# ProPrj_15_v2_0_2025-09-09.net
KiCad netlist of a schematic drawn in EasyEDA Pro
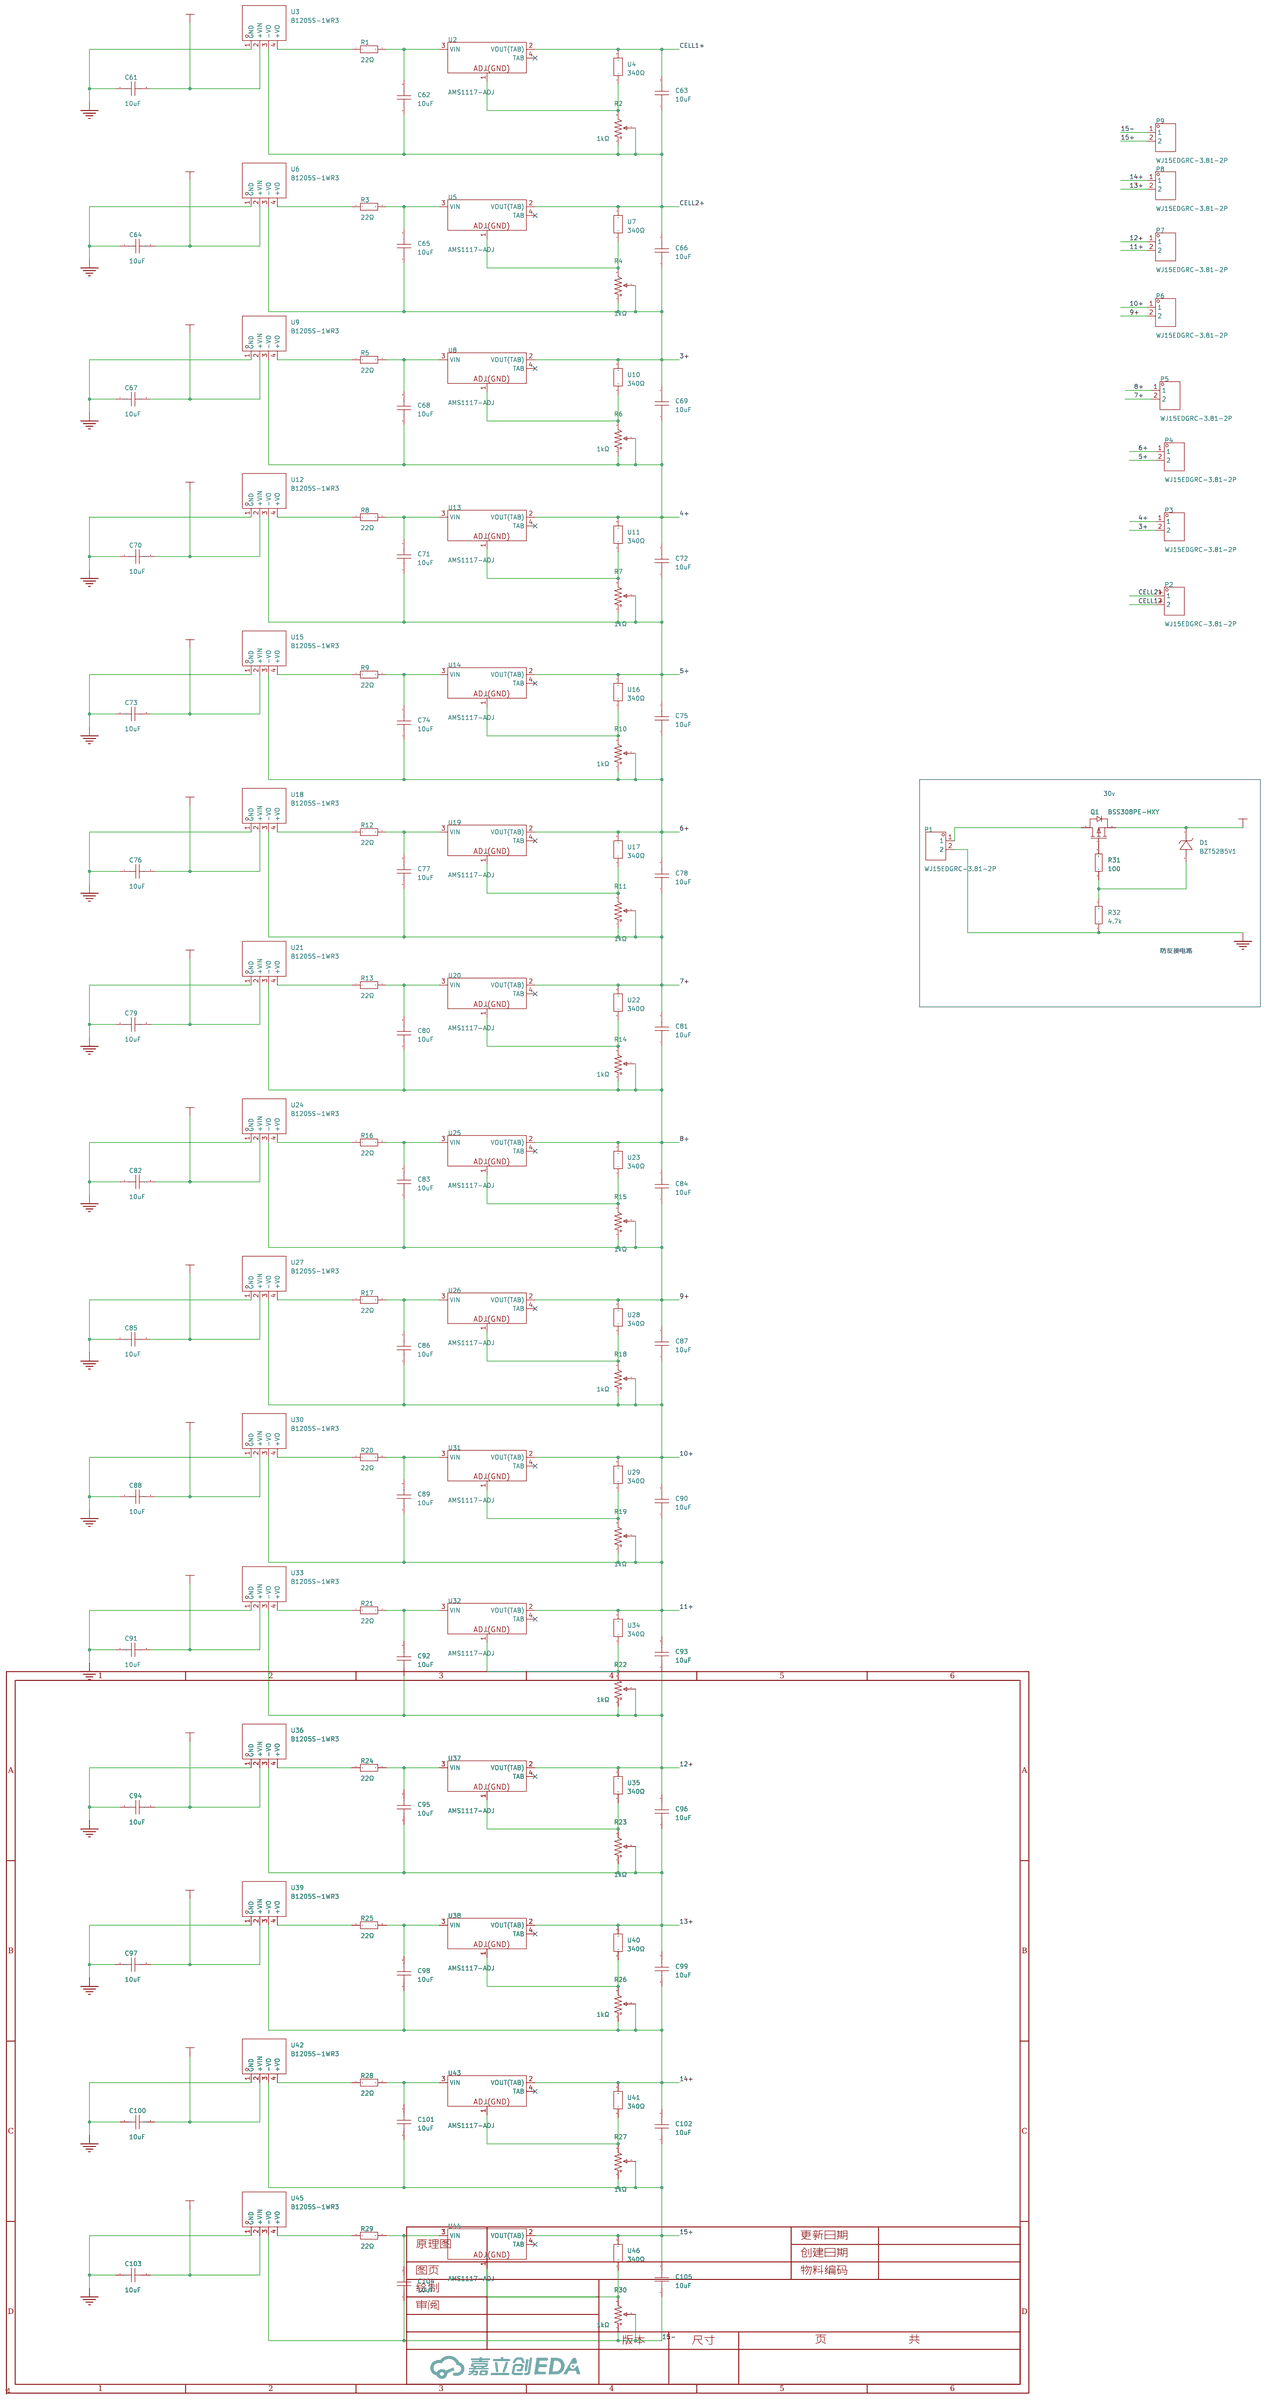
[diagram p0: schematic sheet]

(export (version "E")
  (design (tool "Eeschema 10.0.6"))
  (components
    (comp (ref "C61")
      (value "10uF")
      (footprint "easyedapro:C0805")
      (description "容值:10uF;精度:±10%;额定电压:25V;材质(温度系数):X5R;")
      (fields
        (field (name "Manufacturer Part") "CL21A106KAYNNNE")
        (field (name "Manufacturer") "SAMSUNG(三星)")
      )
      (libsource (lib "easyedapro") (part "CL21A106KAYNNNE"))
    )
    (comp (ref "C62")
      (value "10uF")
      (footprint "easyedapro:C0805")
      (description "容值:10uF;精度:±10%;额定电压:25V;材质(温度系数):X5R;")
      (fields
        (field (name "Manufacturer Part") "CL21A106KAYNNNE")
        (field (name "Manufacturer") "SAMSUNG(三星)")
      )
      (libsource (lib "easyedapro") (part "CL21A106KAYNNNE"))
    )
    (comp (ref "C63")
      (value "10uF")
      (footprint "easyedapro:C0805")
      (description "容值:10uF;精度:±10%;额定电压:25V;材质(温度系数):X5R;")
      (fields
        (field (name "Manufacturer Part") "CL21A106KAYNNNE")
        (field (name "Manufacturer") "SAMSUNG(三星)")
      )
      (libsource (lib "easyedapro") (part "CL21A106KAYNNNE"))
    )
    (comp (ref "C64")
      (value "10uF")
      (footprint "easyedapro:C0805")
      (description "容值:10uF;精度:±10%;额定电压:25V;材质(温度系数):X5R;")
      (fields
        (field (name "Manufacturer Part") "CL21A106KAYNNNE")
        (field (name "Manufacturer") "SAMSUNG(三星)")
      )
      (libsource (lib "easyedapro") (part "CL21A106KAYNNNE"))
    )
    (comp (ref "C65")
      (value "10uF")
      (footprint "easyedapro:C0805")
      (description "容值:10uF;精度:±10%;额定电压:25V;材质(温度系数):X5R;")
      (fields
        (field (name "Manufacturer Part") "CL21A106KAYNNNE")
        (field (name "Manufacturer") "SAMSUNG(三星)")
      )
      (libsource (lib "easyedapro") (part "CL21A106KAYNNNE"))
    )
    (comp (ref "C66")
      (value "10uF")
      (footprint "easyedapro:C0805")
      (description "容值:10uF;精度:±10%;额定电压:25V;材质(温度系数):X5R;")
      (fields
        (field (name "Manufacturer Part") "CL21A106KAYNNNE")
        (field (name "Manufacturer") "SAMSUNG(三星)")
      )
      (libsource (lib "easyedapro") (part "CL21A106KAYNNNE"))
    )
    (comp (ref "C67")
      (value "10uF")
      (footprint "easyedapro:C0805")
      (description "容值:10uF;精度:±10%;额定电压:25V;材质(温度系数):X5R;")
      (fields
        (field (name "Manufacturer Part") "CL21A106KAYNNNE")
        (field (name "Manufacturer") "SAMSUNG(三星)")
      )
      (libsource (lib "easyedapro") (part "CL21A106KAYNNNE"))
    )
    (comp (ref "C68")
      (value "10uF")
      (footprint "easyedapro:C0805")
      (description "容值:10uF;精度:±10%;额定电压:25V;材质(温度系数):X5R;")
      (fields
        (field (name "Manufacturer Part") "CL21A106KAYNNNE")
        (field (name "Manufacturer") "SAMSUNG(三星)")
      )
      (libsource (lib "easyedapro") (part "CL21A106KAYNNNE"))
    )
    (comp (ref "C69")
      (value "10uF")
      (footprint "easyedapro:C0805")
      (description "容值:10uF;精度:±10%;额定电压:25V;材质(温度系数):X5R;")
      (fields
        (field (name "Manufacturer Part") "CL21A106KAYNNNE")
        (field (name "Manufacturer") "SAMSUNG(三星)")
      )
      (libsource (lib "easyedapro") (part "CL21A106KAYNNNE"))
    )
    (comp (ref "C70")
      (value "10uF")
      (footprint "easyedapro:C0805")
      (description "容值:10uF;精度:±10%;额定电压:25V;材质(温度系数):X5R;")
      (fields
        (field (name "Manufacturer Part") "CL21A106KAYNNNE")
        (field (name "Manufacturer") "SAMSUNG(三星)")
      )
      (libsource (lib "easyedapro") (part "CL21A106KAYNNNE"))
    )
    (comp (ref "C71")
      (value "10uF")
      (footprint "easyedapro:C0805")
      (description "容值:10uF;精度:±10%;额定电压:25V;材质(温度系数):X5R;")
      (fields
        (field (name "Manufacturer Part") "CL21A106KAYNNNE")
        (field (name "Manufacturer") "SAMSUNG(三星)")
      )
      (libsource (lib "easyedapro") (part "CL21A106KAYNNNE"))
    )
    (comp (ref "C72")
      (value "10uF")
      (footprint "easyedapro:C0805")
      (description "容值:10uF;精度:±10%;额定电压:25V;材质(温度系数):X5R;")
      (fields
        (field (name "Manufacturer Part") "CL21A106KAYNNNE")
        (field (name "Manufacturer") "SAMSUNG(三星)")
      )
      (libsource (lib "easyedapro") (part "CL21A106KAYNNNE"))
    )
    (comp (ref "C73")
      (value "10uF")
      (footprint "easyedapro:C0805")
      (description "容值:10uF;精度:±10%;额定电压:25V;材质(温度系数):X5R;")
      (fields
        (field (name "Manufacturer Part") "CL21A106KAYNNNE")
        (field (name "Manufacturer") "SAMSUNG(三星)")
      )
      (libsource (lib "easyedapro") (part "CL21A106KAYNNNE"))
    )
    (comp (ref "C74")
      (value "10uF")
      (footprint "easyedapro:C0805")
      (description "容值:10uF;精度:±10%;额定电压:25V;材质(温度系数):X5R;")
      (fields
        (field (name "Manufacturer Part") "CL21A106KAYNNNE")
        (field (name "Manufacturer") "SAMSUNG(三星)")
      )
      (libsource (lib "easyedapro") (part "CL21A106KAYNNNE"))
    )
    (comp (ref "C75")
      (value "10uF")
      (footprint "easyedapro:C0805")
      (description "容值:10uF;精度:±10%;额定电压:25V;材质(温度系数):X5R;")
      (fields
        (field (name "Manufacturer Part") "CL21A106KAYNNNE")
        (field (name "Manufacturer") "SAMSUNG(三星)")
      )
      (libsource (lib "easyedapro") (part "CL21A106KAYNNNE"))
    )
    (comp (ref "C76")
      (value "10uF")
      (footprint "easyedapro:C0805")
      (description "容值:10uF;精度:±10%;额定电压:25V;材质(温度系数):X5R;")
      (fields
        (field (name "Manufacturer Part") "CL21A106KAYNNNE")
        (field (name "Manufacturer") "SAMSUNG(三星)")
      )
      (libsource (lib "easyedapro") (part "CL21A106KAYNNNE"))
    )
    (comp (ref "C77")
      (value "10uF")
      (footprint "easyedapro:C0805")
      (description "容值:10uF;精度:±10%;额定电压:25V;材质(温度系数):X5R;")
      (fields
        (field (name "Manufacturer Part") "CL21A106KAYNNNE")
        (field (name "Manufacturer") "SAMSUNG(三星)")
      )
      (libsource (lib "easyedapro") (part "CL21A106KAYNNNE"))
    )
    (comp (ref "C78")
      (value "10uF")
      (footprint "easyedapro:C0805")
      (description "容值:10uF;精度:±10%;额定电压:25V;材质(温度系数):X5R;")
      (fields
        (field (name "Manufacturer Part") "CL21A106KAYNNNE")
        (field (name "Manufacturer") "SAMSUNG(三星)")
      )
      (libsource (lib "easyedapro") (part "CL21A106KAYNNNE"))
    )
    (comp (ref "C79")
      (value "10uF")
      (footprint "easyedapro:C0805")
      (description "容值:10uF;精度:±10%;额定电压:25V;材质(温度系数):X5R;")
      (fields
        (field (name "Manufacturer Part") "CL21A106KAYNNNE")
        (field (name "Manufacturer") "SAMSUNG(三星)")
      )
      (libsource (lib "easyedapro") (part "CL21A106KAYNNNE"))
    )
    (comp (ref "C80")
      (value "10uF")
      (footprint "easyedapro:C0805")
      (description "容值:10uF;精度:±10%;额定电压:25V;材质(温度系数):X5R;")
      (fields
        (field (name "Manufacturer Part") "CL21A106KAYNNNE")
        (field (name "Manufacturer") "SAMSUNG(三星)")
      )
      (libsource (lib "easyedapro") (part "CL21A106KAYNNNE"))
    )
    (comp (ref "C81")
      (value "10uF")
      (footprint "easyedapro:C0805")
      (description "容值:10uF;精度:±10%;额定电压:25V;材质(温度系数):X5R;")
      (fields
        (field (name "Manufacturer Part") "CL21A106KAYNNNE")
        (field (name "Manufacturer") "SAMSUNG(三星)")
      )
      (libsource (lib "easyedapro") (part "CL21A106KAYNNNE"))
    )
    (comp (ref "C82")
      (value "10uF")
      (footprint "easyedapro:C0805")
      (description "容值:10uF;精度:±10%;额定电压:25V;材质(温度系数):X5R;")
      (fields
        (field (name "Manufacturer Part") "CL21A106KAYNNNE")
        (field (name "Manufacturer") "SAMSUNG(三星)")
      )
      (libsource (lib "easyedapro") (part "CL21A106KAYNNNE"))
    )
    (comp (ref "C83")
      (value "10uF")
      (footprint "easyedapro:C0805")
      (description "容值:10uF;精度:±10%;额定电压:25V;材质(温度系数):X5R;")
      (fields
        (field (name "Manufacturer Part") "CL21A106KAYNNNE")
        (field (name "Manufacturer") "SAMSUNG(三星)")
      )
      (libsource (lib "easyedapro") (part "CL21A106KAYNNNE"))
    )
    (comp (ref "C84")
      (value "10uF")
      (footprint "easyedapro:C0805")
      (description "容值:10uF;精度:±10%;额定电压:25V;材质(温度系数):X5R;")
      (fields
        (field (name "Manufacturer Part") "CL21A106KAYNNNE")
        (field (name "Manufacturer") "SAMSUNG(三星)")
      )
      (libsource (lib "easyedapro") (part "CL21A106KAYNNNE"))
    )
    (comp (ref "C85")
      (value "10uF")
      (footprint "easyedapro:C0805")
      (description "容值:10uF;精度:±10%;额定电压:25V;材质(温度系数):X5R;")
      (fields
        (field (name "Manufacturer Part") "CL21A106KAYNNNE")
        (field (name "Manufacturer") "SAMSUNG(三星)")
      )
      (libsource (lib "easyedapro") (part "CL21A106KAYNNNE"))
    )
    (comp (ref "C86")
      (value "10uF")
      (footprint "easyedapro:C0805")
      (description "容值:10uF;精度:±10%;额定电压:25V;材质(温度系数):X5R;")
      (fields
        (field (name "Manufacturer Part") "CL21A106KAYNNNE")
        (field (name "Manufacturer") "SAMSUNG(三星)")
      )
      (libsource (lib "easyedapro") (part "CL21A106KAYNNNE"))
    )
    (comp (ref "C87")
      (value "10uF")
      (footprint "easyedapro:C0805")
      (description "容值:10uF;精度:±10%;额定电压:25V;材质(温度系数):X5R;")
      (fields
        (field (name "Manufacturer Part") "CL21A106KAYNNNE")
        (field (name "Manufacturer") "SAMSUNG(三星)")
      )
      (libsource (lib "easyedapro") (part "CL21A106KAYNNNE"))
    )
    (comp (ref "C88")
      (value "10uF")
      (footprint "easyedapro:C0805")
      (description "容值:10uF;精度:±10%;额定电压:25V;材质(温度系数):X5R;")
      (fields
        (field (name "Manufacturer Part") "CL21A106KAYNNNE")
        (field (name "Manufacturer") "SAMSUNG(三星)")
      )
      (libsource (lib "easyedapro") (part "CL21A106KAYNNNE"))
    )
    (comp (ref "C89")
      (value "10uF")
      (footprint "easyedapro:C0805")
      (description "容值:10uF;精度:±10%;额定电压:25V;材质(温度系数):X5R;")
      (fields
        (field (name "Manufacturer Part") "CL21A106KAYNNNE")
        (field (name "Manufacturer") "SAMSUNG(三星)")
      )
      (libsource (lib "easyedapro") (part "CL21A106KAYNNNE"))
    )
    (comp (ref "C90")
      (value "10uF")
      (footprint "easyedapro:C0805")
      (description "容值:10uF;精度:±10%;额定电压:25V;材质(温度系数):X5R;")
      (fields
        (field (name "Manufacturer Part") "CL21A106KAYNNNE")
        (field (name "Manufacturer") "SAMSUNG(三星)")
      )
      (libsource (lib "easyedapro") (part "CL21A106KAYNNNE"))
    )
    (comp (ref "C91")
      (value "10uF")
      (footprint "easyedapro:C0805")
      (description "容值:10uF;精度:±10%;额定电压:25V;材质(温度系数):X5R;")
      (fields
        (field (name "Manufacturer Part") "CL21A106KAYNNNE")
        (field (name "Manufacturer") "SAMSUNG(三星)")
      )
      (libsource (lib "easyedapro") (part "CL21A106KAYNNNE"))
    )
    (comp (ref "C92")
      (value "10uF")
      (footprint "easyedapro:C0805")
      (description "容值:10uF;精度:±10%;额定电压:25V;材质(温度系数):X5R;")
      (fields
        (field (name "Manufacturer Part") "CL21A106KAYNNNE")
        (field (name "Manufacturer") "SAMSUNG(三星)")
      )
      (libsource (lib "easyedapro") (part "CL21A106KAYNNNE"))
    )
    (comp (ref "C93")
      (value "10uF")
      (footprint "easyedapro:C0805")
      (description "容值:10uF;精度:±10%;额定电压:25V;材质(温度系数):X5R;")
      (fields
        (field (name "Manufacturer Part") "CL21A106KAYNNNE")
        (field (name "Manufacturer") "SAMSUNG(三星)")
      )
      (libsource (lib "easyedapro") (part "CL21A106KAYNNNE"))
    )
    (comp (ref "C94")
      (value "10uF")
      (footprint "easyedapro:C0805")
      (description "容值:10uF;精度:±10%;额定电压:25V;材质(温度系数):X5R;")
      (fields
        (field (name "Manufacturer Part") "CL21A106KAYNNNE")
        (field (name "Manufacturer") "SAMSUNG(三星)")
      )
      (libsource (lib "easyedapro") (part "CL21A106KAYNNNE"))
    )
    (comp (ref "C95")
      (value "10uF")
      (footprint "easyedapro:C0805")
      (description "容值:10uF;精度:±10%;额定电压:25V;材质(温度系数):X5R;")
      (fields
        (field (name "Manufacturer Part") "CL21A106KAYNNNE")
        (field (name "Manufacturer") "SAMSUNG(三星)")
      )
      (libsource (lib "easyedapro") (part "CL21A106KAYNNNE"))
    )
    (comp (ref "C96")
      (value "10uF")
      (footprint "easyedapro:C0805")
      (description "容值:10uF;精度:±10%;额定电压:25V;材质(温度系数):X5R;")
      (fields
        (field (name "Manufacturer Part") "CL21A106KAYNNNE")
        (field (name "Manufacturer") "SAMSUNG(三星)")
      )
      (libsource (lib "easyedapro") (part "CL21A106KAYNNNE"))
    )
    (comp (ref "C97")
      (value "10uF")
      (footprint "easyedapro:C0805")
      (description "容值:10uF;精度:±10%;额定电压:25V;材质(温度系数):X5R;")
      (fields
        (field (name "Manufacturer Part") "CL21A106KAYNNNE")
        (field (name "Manufacturer") "SAMSUNG(三星)")
      )
      (libsource (lib "easyedapro") (part "CL21A106KAYNNNE"))
    )
    (comp (ref "C98")
      (value "10uF")
      (footprint "easyedapro:C0805")
      (description "容值:10uF;精度:±10%;额定电压:25V;材质(温度系数):X5R;")
      (fields
        (field (name "Manufacturer Part") "CL21A106KAYNNNE")
        (field (name "Manufacturer") "SAMSUNG(三星)")
      )
      (libsource (lib "easyedapro") (part "CL21A106KAYNNNE"))
    )
    (comp (ref "C99")
      (value "10uF")
      (footprint "easyedapro:C0805")
      (description "容值:10uF;精度:±10%;额定电压:25V;材质(温度系数):X5R;")
      (fields
        (field (name "Manufacturer Part") "CL21A106KAYNNNE")
        (field (name "Manufacturer") "SAMSUNG(三星)")
      )
      (libsource (lib "easyedapro") (part "CL21A106KAYNNNE"))
    )
    (comp (ref "C100")
      (value "10uF")
      (footprint "easyedapro:C0805")
      (description "容值:10uF;精度:±10%;额定电压:25V;材质(温度系数):X5R;")
      (fields
        (field (name "Manufacturer Part") "CL21A106KAYNNNE")
        (field (name "Manufacturer") "SAMSUNG(三星)")
      )
      (libsource (lib "easyedapro") (part "CL21A106KAYNNNE"))
    )
    (comp (ref "C101")
      (value "10uF")
      (footprint "easyedapro:C0805")
      (description "容值:10uF;精度:±10%;额定电压:25V;材质(温度系数):X5R;")
      (fields
        (field (name "Manufacturer Part") "CL21A106KAYNNNE")
        (field (name "Manufacturer") "SAMSUNG(三星)")
      )
      (libsource (lib "easyedapro") (part "CL21A106KAYNNNE"))
    )
    (comp (ref "C102")
      (value "10uF")
      (footprint "easyedapro:C0805")
      (description "容值:10uF;精度:±10%;额定电压:25V;材质(温度系数):X5R;")
      (fields
        (field (name "Manufacturer Part") "CL21A106KAYNNNE")
        (field (name "Manufacturer") "SAMSUNG(三星)")
      )
      (libsource (lib "easyedapro") (part "CL21A106KAYNNNE"))
    )
    (comp (ref "C103")
      (value "10uF")
      (footprint "easyedapro:C0805")
      (description "容值:10uF;精度:±10%;额定电压:25V;材质(温度系数):X5R;")
      (fields
        (field (name "Manufacturer Part") "CL21A106KAYNNNE")
        (field (name "Manufacturer") "SAMSUNG(三星)")
      )
      (libsource (lib "easyedapro") (part "CL21A106KAYNNNE"))
    )
    (comp (ref "C104")
      (value "10uF")
      (footprint "easyedapro:C0805")
      (description "容值:10uF;精度:±10%;额定电压:25V;材质(温度系数):X5R;")
      (fields
        (field (name "Manufacturer Part") "CL21A106KAYNNNE")
        (field (name "Manufacturer") "SAMSUNG(三星)")
      )
      (libsource (lib "easyedapro") (part "CL21A106KAYNNNE"))
    )
    (comp (ref "C105")
      (value "10uF")
      (footprint "easyedapro:C0805")
      (description "容值:10uF;精度:±10%;额定电压:25V;材质(温度系数):X5R;")
      (fields
        (field (name "Manufacturer Part") "CL21A106KAYNNNE")
        (field (name "Manufacturer") "SAMSUNG(三星)")
      )
      (libsource (lib "easyedapro") (part "CL21A106KAYNNNE"))
    )
    (comp (ref "D1")
      (value "BZT52B5V1")
      (footprint "easyedapro:SOD-123_L2.7-W1.6-LS3.7-RD")
      (description "二极管配置:独立式;稳压值(标称值):5.1V;稳压值(范围):5V~5.2V;耗散功率(Pd):500mW;")
      (fields (field (name "Manufacturer") "宏嘉诚"))
      (libsource (lib "easyedapro") (part "BZT52B5V1_C19077393"))
    )
    (comp (ref "P1")
      (value "WJ15EDGRC-3.81-2P")
      (footprint "easyedapro:CONN-TH_2P-P3.81_WJ15EDGRC-3.81-2P")
      (fields (field (name "Manufacturer") "KANGNEX(康奈克斯电气)"))
      (libsource (lib "easyedapro") (part "WJ15EDGRC-3.81-2P"))
    )
    (comp (ref "P2")
      (value "WJ15EDGRC-3.81-2P")
      (footprint "easyedapro:CONN-TH_2P-P3.81_WJ15EDGRC-3.81-2P")
      (fields (field (name "Manufacturer") "KANGNEX(康奈克斯电气)"))
      (libsource (lib "easyedapro") (part "WJ15EDGRC-3.81-2P"))
    )
    (comp (ref "P3")
      (value "WJ15EDGRC-3.81-2P")
      (footprint "easyedapro:CONN-TH_2P-P3.81_WJ15EDGRC-3.81-2P")
      (fields (field (name "Manufacturer") "KANGNEX(康奈克斯电气)"))
      (libsource (lib "easyedapro") (part "WJ15EDGRC-3.81-2P"))
    )
    (comp (ref "P4")
      (value "WJ15EDGRC-3.81-2P")
      (footprint "easyedapro:CONN-TH_2P-P3.81_WJ15EDGRC-3.81-2P")
      (fields (field (name "Manufacturer") "KANGNEX(康奈克斯电气)"))
      (libsource (lib "easyedapro") (part "WJ15EDGRC-3.81-2P"))
    )
    (comp (ref "P5")
      (value "WJ15EDGRC-3.81-2P")
      (footprint "easyedapro:CONN-TH_2P-P3.81_WJ15EDGRC-3.81-2P")
      (fields (field (name "Manufacturer") "KANGNEX(康奈克斯电气)"))
      (libsource (lib "easyedapro") (part "WJ15EDGRC-3.81-2P"))
    )
    (comp (ref "P6")
      (value "WJ15EDGRC-3.81-2P")
      (footprint "easyedapro:CONN-TH_2P-P3.81_WJ15EDGRC-3.81-2P")
      (fields (field (name "Manufacturer") "KANGNEX(康奈克斯电气)"))
      (libsource (lib "easyedapro") (part "WJ15EDGRC-3.81-2P"))
    )
    (comp (ref "P7")
      (value "WJ15EDGRC-3.81-2P")
      (footprint "easyedapro:CONN-TH_2P-P3.81_WJ15EDGRC-3.81-2P")
      (fields (field (name "Manufacturer") "KANGNEX(康奈克斯电气)"))
      (libsource (lib "easyedapro") (part "WJ15EDGRC-3.81-2P"))
    )
    (comp (ref "P8")
      (value "WJ15EDGRC-3.81-2P")
      (footprint "easyedapro:CONN-TH_2P-P3.81_WJ15EDGRC-3.81-2P")
      (fields (field (name "Manufacturer") "KANGNEX(康奈克斯电气)"))
      (libsource (lib "easyedapro") (part "WJ15EDGRC-3.81-2P"))
    )
    (comp (ref "P9")
      (value "WJ15EDGRC-3.81-2P")
      (footprint "easyedapro:CONN-TH_2P-P3.81_WJ15EDGRC-3.81-2P")
      (fields (field (name "Manufacturer") "KANGNEX(康奈克斯电气)"))
      (libsource (lib "easyedapro") (part "WJ15EDGRC-3.81-2P"))
    )
    (comp (ref "Q1")
      (value "BSS308PE-HXY")
      (footprint "easyedapro:SOT-23-3_L2.9-W1.3-P1.90-LS2.4-BR")
      (fields (field (name "Manufacturer") "HXY MOSFET(华轩阳电子)"))
      (libsource (lib "easyedapro") (part "BSS308PE-HXY"))
    )
    (comp (ref "R1")
      (value "22Ω")
      (footprint "easyedapro:R0805")
      (description "电阻类型:厚膜电阻;阻值:22Ω;精度:±5%;功率:125mW;最大工作电压:150V;温度系数:±200ppm/°C;")
      (fields
        (field (name "Manufacturer Part") "0805W8J0220T5E")
        (field (name "Manufacturer") "UNI-ROYAL(厚声)")
      )
      (libsource (lib "easyedapro") (part "0805W8J0220T5E"))
    )
    (comp (ref "R2")
      (value "1kΩ")
      (footprint "easyedapro:RES-ADJ-TH_3296W")
      (description "阻值:1kΩ;精度:±10%;功率:500mW;")
      (fields (field (name "Manufacturer Part") "3296W-1-102-8mm") (field (name "Manufacturer") "BOCHEN(博晨)"))
      (libsource (lib "easyedapro") (part "3296W-1-102_C2766201"))
    )
    (comp (ref "R3")
      (value "22Ω")
      (footprint "easyedapro:R0805")
      (description "电阻类型:厚膜电阻;阻值:22Ω;精度:±5%;功率:125mW;最大工作电压:150V;温度系数:±200ppm/°C;")
      (fields
        (field (name "Manufacturer Part") "0805W8J0220T5E")
        (field (name "Manufacturer") "UNI-ROYAL(厚声)")
      )
      (libsource (lib "easyedapro") (part "0805W8J0220T5E"))
    )
    (comp (ref "R4")
      (value "1kΩ")
      (footprint "easyedapro:RES-ADJ-TH_3296W")
      (description "阻值:1kΩ;精度:±10%;功率:500mW;")
      (fields (field (name "Manufacturer Part") "3296W-1-102-8mm") (field (name "Manufacturer") "BOCHEN(博晨)"))
      (libsource (lib "easyedapro") (part "3296W-1-102_C2766201"))
    )
    (comp (ref "R5")
      (value "22Ω")
      (footprint "easyedapro:R0805")
      (description "电阻类型:厚膜电阻;阻值:22Ω;精度:±5%;功率:125mW;最大工作电压:150V;温度系数:±200ppm/°C;")
      (fields
        (field (name "Manufacturer Part") "0805W8J0220T5E")
        (field (name "Manufacturer") "UNI-ROYAL(厚声)")
      )
      (libsource (lib "easyedapro") (part "0805W8J0220T5E"))
    )
    (comp (ref "R6")
      (value "1kΩ")
      (footprint "easyedapro:RES-ADJ-TH_3296W")
      (description "阻值:1kΩ;精度:±10%;功率:500mW;")
      (fields (field (name "Manufacturer Part") "3296W-1-102-8mm") (field (name "Manufacturer") "BOCHEN(博晨)"))
      (libsource (lib "easyedapro") (part "3296W-1-102_C2766201"))
    )
    (comp (ref "R7")
      (value "1kΩ")
      (footprint "easyedapro:RES-ADJ-TH_3296W")
      (description "阻值:1kΩ;精度:±10%;功率:500mW;")
      (fields (field (name "Manufacturer Part") "3296W-1-102-8mm") (field (name "Manufacturer") "BOCHEN(博晨)"))
      (libsource (lib "easyedapro") (part "3296W-1-102_C2766201"))
    )
    (comp (ref "R8")
      (value "22Ω")
      (footprint "easyedapro:R0805")
      (description "电阻类型:厚膜电阻;阻值:22Ω;精度:±5%;功率:125mW;最大工作电压:150V;温度系数:±200ppm/°C;")
      (fields
        (field (name "Manufacturer Part") "0805W8J0220T5E")
        (field (name "Manufacturer") "UNI-ROYAL(厚声)")
      )
      (libsource (lib "easyedapro") (part "0805W8J0220T5E"))
    )
    (comp (ref "R9")
      (value "22Ω")
      (footprint "easyedapro:R0805")
      (description "电阻类型:厚膜电阻;阻值:22Ω;精度:±5%;功率:125mW;最大工作电压:150V;温度系数:±200ppm/°C;")
      (fields
        (field (name "Manufacturer Part") "0805W8J0220T5E")
        (field (name "Manufacturer") "UNI-ROYAL(厚声)")
      )
      (libsource (lib "easyedapro") (part "0805W8J0220T5E"))
    )
    (comp (ref "R10")
      (value "1kΩ")
      (footprint "easyedapro:RES-ADJ-TH_3296W")
      (description "阻值:1kΩ;精度:±10%;功率:500mW;")
      (fields (field (name "Manufacturer Part") "3296W-1-102-8mm") (field (name "Manufacturer") "BOCHEN(博晨)"))
      (libsource (lib "easyedapro") (part "3296W-1-102_C2766201"))
    )
    (comp (ref "R11")
      (value "1kΩ")
      (footprint "easyedapro:RES-ADJ-TH_3296W")
      (description "阻值:1kΩ;精度:±10%;功率:500mW;")
      (fields (field (name "Manufacturer Part") "3296W-1-102-8mm") (field (name "Manufacturer") "BOCHEN(博晨)"))
      (libsource (lib "easyedapro") (part "3296W-1-102_C2766201"))
    )
    (comp (ref "R12")
      (value "22Ω")
      (footprint "easyedapro:R0805")
      (description "电阻类型:厚膜电阻;阻值:22Ω;精度:±5%;功率:125mW;最大工作电压:150V;温度系数:±200ppm/°C;")
      (fields
        (field (name "Manufacturer Part") "0805W8J0220T5E")
        (field (name "Manufacturer") "UNI-ROYAL(厚声)")
      )
      (libsource (lib "easyedapro") (part "0805W8J0220T5E"))
    )
    (comp (ref "R13")
      (value "22Ω")
      (footprint "easyedapro:R0805")
      (description "电阻类型:厚膜电阻;阻值:22Ω;精度:±5%;功率:125mW;最大工作电压:150V;温度系数:±200ppm/°C;")
      (fields
        (field (name "Manufacturer Part") "0805W8J0220T5E")
        (field (name "Manufacturer") "UNI-ROYAL(厚声)")
      )
      (libsource (lib "easyedapro") (part "0805W8J0220T5E"))
    )
    (comp (ref "R14")
      (value "1kΩ")
      (footprint "easyedapro:RES-ADJ-TH_3296W")
      (description "阻值:1kΩ;精度:±10%;功率:500mW;")
      (fields (field (name "Manufacturer Part") "3296W-1-102-8mm") (field (name "Manufacturer") "BOCHEN(博晨)"))
      (libsource (lib "easyedapro") (part "3296W-1-102_C2766201"))
    )
    (comp (ref "R15")
      (value "1kΩ")
      (footprint "easyedapro:RES-ADJ-TH_3296W")
      (description "阻值:1kΩ;精度:±10%;功率:500mW;")
      (fields (field (name "Manufacturer Part") "3296W-1-102-8mm") (field (name "Manufacturer") "BOCHEN(博晨)"))
      (libsource (lib "easyedapro") (part "3296W-1-102_C2766201"))
    )
    (comp (ref "R16")
      (value "22Ω")
      (footprint "easyedapro:R0805")
      (description "电阻类型:厚膜电阻;阻值:22Ω;精度:±5%;功率:125mW;最大工作电压:150V;温度系数:±200ppm/°C;")
      (fields
        (field (name "Manufacturer Part") "0805W8J0220T5E")
        (field (name "Manufacturer") "UNI-ROYAL(厚声)")
      )
      (libsource (lib "easyedapro") (part "0805W8J0220T5E"))
    )
    (comp (ref "R17")
      (value "22Ω")
      (footprint "easyedapro:R0805")
      (description "电阻类型:厚膜电阻;阻值:22Ω;精度:±5%;功率:125mW;最大工作电压:150V;温度系数:±200ppm/°C;")
      (fields
        (field (name "Manufacturer Part") "0805W8J0220T5E")
        (field (name "Manufacturer") "UNI-ROYAL(厚声)")
      )
      (libsource (lib "easyedapro") (part "0805W8J0220T5E"))
    )
    (comp (ref "R18")
      (value "1kΩ")
      (footprint "easyedapro:RES-ADJ-TH_3296W")
      (description "阻值:1kΩ;精度:±10%;功率:500mW;")
      (fields (field (name "Manufacturer Part") "3296W-1-102-8mm") (field (name "Manufacturer") "BOCHEN(博晨)"))
      (libsource (lib "easyedapro") (part "3296W-1-102_C2766201"))
    )
    (comp (ref "R19")
      (value "1kΩ")
      (footprint "easyedapro:RES-ADJ-TH_3296W")
      (description "阻值:1kΩ;精度:±10%;功率:500mW;")
      (fields (field (name "Manufacturer Part") "3296W-1-102-8mm") (field (name "Manufacturer") "BOCHEN(博晨)"))
      (libsource (lib "easyedapro") (part "3296W-1-102_C2766201"))
    )
    (comp (ref "R20")
      (value "22Ω")
      (footprint "easyedapro:R0805")
      (description "电阻类型:厚膜电阻;阻值:22Ω;精度:±5%;功率:125mW;最大工作电压:150V;温度系数:±200ppm/°C;")
      (fields
        (field (name "Manufacturer Part") "0805W8J0220T5E")
        (field (name "Manufacturer") "UNI-ROYAL(厚声)")
      )
      (libsource (lib "easyedapro") (part "0805W8J0220T5E"))
    )
    (comp (ref "R21")
      (value "22Ω")
      (footprint "easyedapro:R0805")
      (description "电阻类型:厚膜电阻;阻值:22Ω;精度:±5%;功率:125mW;最大工作电压:150V;温度系数:±200ppm/°C;")
      (fields
        (field (name "Manufacturer Part") "0805W8J0220T5E")
        (field (name "Manufacturer") "UNI-ROYAL(厚声)")
      )
      (libsource (lib "easyedapro") (part "0805W8J0220T5E"))
    )
    (comp (ref "R22")
      (value "1kΩ")
      (footprint "easyedapro:RES-ADJ-TH_3296W")
      (description "阻值:1kΩ;精度:±10%;功率:500mW;")
      (fields (field (name "Manufacturer Part") "3296W-1-102-8mm") (field (name "Manufacturer") "BOCHEN(博晨)"))
      (libsource (lib "easyedapro") (part "3296W-1-102_C2766201"))
    )
    (comp (ref "R23")
      (value "1kΩ")
      (footprint "easyedapro:RES-ADJ-TH_3296W")
      (description "阻值:1kΩ;精度:±10%;功率:500mW;")
      (fields (field (name "Manufacturer Part") "3296W-1-102-8mm") (field (name "Manufacturer") "BOCHEN(博晨)"))
      (libsource (lib "easyedapro") (part "3296W-1-102_C2766201"))
    )
    (comp (ref "R24")
      (value "22Ω")
      (footprint "easyedapro:R0805")
      (description "电阻类型:厚膜电阻;阻值:22Ω;精度:±5%;功率:125mW;最大工作电压:150V;温度系数:±200ppm/°C;")
      (fields
        (field (name "Manufacturer Part") "0805W8J0220T5E")
        (field (name "Manufacturer") "UNI-ROYAL(厚声)")
      )
      (libsource (lib "easyedapro") (part "0805W8J0220T5E"))
    )
    (comp (ref "R25")
      (value "22Ω")
      (footprint "easyedapro:R0805")
      (description "电阻类型:厚膜电阻;阻值:22Ω;精度:±5%;功率:125mW;最大工作电压:150V;温度系数:±200ppm/°C;")
      (fields
        (field (name "Manufacturer Part") "0805W8J0220T5E")
        (field (name "Manufacturer") "UNI-ROYAL(厚声)")
      )
      (libsource (lib "easyedapro") (part "0805W8J0220T5E"))
    )
    (comp (ref "R26")
      (value "1kΩ")
      (footprint "easyedapro:RES-ADJ-TH_3296W")
      (description "阻值:1kΩ;精度:±10%;功率:500mW;")
      (fields (field (name "Manufacturer Part") "3296W-1-102-8mm") (field (name "Manufacturer") "BOCHEN(博晨)"))
      (libsource (lib "easyedapro") (part "3296W-1-102_C2766201"))
    )
    (comp (ref "R27")
      (value "1kΩ")
      (footprint "easyedapro:RES-ADJ-TH_3296W")
      (description "阻值:1kΩ;精度:±10%;功率:500mW;")
      (fields (field (name "Manufacturer Part") "3296W-1-102-8mm") (field (name "Manufacturer") "BOCHEN(博晨)"))
      (libsource (lib "easyedapro") (part "3296W-1-102_C2766201"))
    )
    (comp (ref "R28")
      (value "22Ω")
      (footprint "easyedapro:R0805")
      (description "电阻类型:厚膜电阻;阻值:22Ω;精度:±5%;功率:125mW;最大工作电压:150V;温度系数:±200ppm/°C;")
      (fields
        (field (name "Manufacturer Part") "0805W8J0220T5E")
        (field (name "Manufacturer") "UNI-ROYAL(厚声)")
      )
      (libsource (lib "easyedapro") (part "0805W8J0220T5E"))
    )
    (comp (ref "R29")
      (value "22Ω")
      (footprint "easyedapro:R0805")
      (description "电阻类型:厚膜电阻;阻值:22Ω;精度:±5%;功率:125mW;最大工作电压:150V;温度系数:±200ppm/°C;")
      (fields
        (field (name "Manufacturer Part") "0805W8J0220T5E")
        (field (name "Manufacturer") "UNI-ROYAL(厚声)")
      )
      (libsource (lib "easyedapro") (part "0805W8J0220T5E"))
    )
    (comp (ref "R30")
      (value "1kΩ")
      (footprint "easyedapro:RES-ADJ-TH_3296W")
      (description "阻值:1kΩ;精度:±10%;功率:500mW;")
      (fields (field (name "Manufacturer Part") "3296W-1-102-8mm") (field (name "Manufacturer") "BOCHEN(博晨)"))
      (libsource (lib "easyedapro") (part "3296W-1-102_C2766201"))
    )
    (comp (ref "R31") (value "100") (footprint "easyedapro:R0805") (libsource (lib "easyedapro") (part "电阻")))
    (comp (ref "R32")
      (value "4.7k")
      (footprint "easyedapro:R0805")
      (libsource (lib "easyedapro") (part "电阻"))
    )
    (comp (ref "U2")
      (value "AMS1117-ADJ")
      (footprint "easyedapro:SOT-223_L6.7-W3.5-P2.30-BR")
      (description "输出类型:可调;工作电压:18V;输出电压:1.25V~10V;输出电流:1A;电源纹波抑制比(PSRR):60dB@(120Hz);输出极性:正极;")
      (fields (field (name "Manufacturer") "UMW(友台半导体)"))
      (libsource (lib "easyedapro") (part "AMS1117-ADJ_C347224"))
    )
    (comp (ref "U3")
      (value "B1205S-1WR3")
      (footprint "easyedapro:PWRM-TH_BXXXXS-1WR3")
      (description "尺寸：11.6*10*6mm 保护方式：短路保护（可持续自恢复）")
      (fields (field (name "Manufacturer") "ZOEYGO(中逸光)"))
      (libsource (lib "easyedapro") (part "B1205S-1WR3_C5264430"))
    )
    (comp (ref "U4")
      (value "340Ω")
      (footprint "easyedapro:R0805")
      (description "电阻类型:厚膜电阻;阻值:340Ω;精度:±1%;功率:125mW;温度系数:±100ppm/°C;")
      (fields (field (name "Manufacturer Part") "FRC0805F3400TS") (field (name "Manufacturer") "FOJAN(富捷)"))
      (libsource (lib "easyedapro") (part "FRC0805F3400TS"))
    )
    (comp (ref "U5")
      (value "AMS1117-ADJ")
      (footprint "easyedapro:SOT-223_L6.7-W3.5-P2.30-BR")
      (description "输出类型:可调;工作电压:18V;输出电压:1.25V~10V;输出电流:1A;电源纹波抑制比(PSRR):60dB@(120Hz);输出极性:正极;")
      (fields (field (name "Manufacturer") "UMW(友台半导体)"))
      (libsource (lib "easyedapro") (part "AMS1117-ADJ_C347224"))
    )
    (comp (ref "U6")
      (value "B1205S-1WR3")
      (footprint "easyedapro:PWRM-TH_BXXXXS-1WR3")
      (description "尺寸：11.6*10*6mm 保护方式：短路保护（可持续自恢复）")
      (fields (field (name "Manufacturer") "ZOEYGO(中逸光)"))
      (libsource (lib "easyedapro") (part "B1205S-1WR3_C5264430"))
    )
    (comp (ref "U7")
      (value "340Ω")
      (footprint "easyedapro:R0805")
      (description "电阻类型:厚膜电阻;阻值:340Ω;精度:±1%;功率:125mW;温度系数:±100ppm/°C;")
      (fields (field (name "Manufacturer Part") "FRC0805F3400TS") (field (name "Manufacturer") "FOJAN(富捷)"))
      (libsource (lib "easyedapro") (part "FRC0805F3400TS"))
    )
    (comp (ref "U8")
      (value "AMS1117-ADJ")
      (footprint "easyedapro:SOT-223_L6.7-W3.5-P2.30-BR")
      (description "输出类型:可调;工作电压:18V;输出电压:1.25V~10V;输出电流:1A;电源纹波抑制比(PSRR):60dB@(120Hz);输出极性:正极;")
      (fields (field (name "Manufacturer") "UMW(友台半导体)"))
      (libsource (lib "easyedapro") (part "AMS1117-ADJ_C347224"))
    )
    (comp (ref "U9")
      (value "B1205S-1WR3")
      (footprint "easyedapro:PWRM-TH_BXXXXS-1WR3")
      (description "尺寸：11.6*10*6mm 保护方式：短路保护（可持续自恢复）")
      (fields (field (name "Manufacturer") "ZOEYGO(中逸光)"))
      (libsource (lib "easyedapro") (part "B1205S-1WR3_C5264430"))
    )
    (comp (ref "U10")
      (value "340Ω")
      (footprint "easyedapro:R0805")
      (description "电阻类型:厚膜电阻;阻值:340Ω;精度:±1%;功率:125mW;温度系数:±100ppm/°C;")
      (fields (field (name "Manufacturer Part") "FRC0805F3400TS") (field (name "Manufacturer") "FOJAN(富捷)"))
      (libsource (lib "easyedapro") (part "FRC0805F3400TS"))
    )
    (comp (ref "U11")
      (value "340Ω")
      (footprint "easyedapro:R0805")
      (description "电阻类型:厚膜电阻;阻值:340Ω;精度:±1%;功率:125mW;温度系数:±100ppm/°C;")
      (fields (field (name "Manufacturer Part") "FRC0805F3400TS") (field (name "Manufacturer") "FOJAN(富捷)"))
      (libsource (lib "easyedapro") (part "FRC0805F3400TS"))
    )
    (comp (ref "U12")
      (value "B1205S-1WR3")
      (footprint "easyedapro:PWRM-TH_BXXXXS-1WR3")
      (description "尺寸：11.6*10*6mm 保护方式：短路保护（可持续自恢复）")
      (fields (field (name "Manufacturer") "ZOEYGO(中逸光)"))
      (libsource (lib "easyedapro") (part "B1205S-1WR3_C5264430"))
    )
    (comp (ref "U13")
      (value "AMS1117-ADJ")
      (footprint "easyedapro:SOT-223_L6.7-W3.5-P2.30-BR")
      (description "输出类型:可调;工作电压:18V;输出电压:1.25V~10V;输出电流:1A;电源纹波抑制比(PSRR):60dB@(120Hz);输出极性:正极;")
      (fields (field (name "Manufacturer") "UMW(友台半导体)"))
      (libsource (lib "easyedapro") (part "AMS1117-ADJ_C347224"))
    )
    (comp (ref "U14")
      (value "AMS1117-ADJ")
      (footprint "easyedapro:SOT-223_L6.7-W3.5-P2.30-BR")
      (description "输出类型:可调;工作电压:18V;输出电压:1.25V~10V;输出电流:1A;电源纹波抑制比(PSRR):60dB@(120Hz);输出极性:正极;")
      (fields (field (name "Manufacturer") "UMW(友台半导体)"))
      (libsource (lib "easyedapro") (part "AMS1117-ADJ_C347224"))
    )
    (comp (ref "U15")
      (value "B1205S-1WR3")
      (footprint "easyedapro:PWRM-TH_BXXXXS-1WR3")
      (description "尺寸：11.6*10*6mm 保护方式：短路保护（可持续自恢复）")
      (fields (field (name "Manufacturer") "ZOEYGO(中逸光)"))
      (libsource (lib "easyedapro") (part "B1205S-1WR3_C5264430"))
    )
    (comp (ref "U16")
      (value "340Ω")
      (footprint "easyedapro:R0805")
      (description "电阻类型:厚膜电阻;阻值:340Ω;精度:±1%;功率:125mW;温度系数:±100ppm/°C;")
      (fields (field (name "Manufacturer Part") "FRC0805F3400TS") (field (name "Manufacturer") "FOJAN(富捷)"))
      (libsource (lib "easyedapro") (part "FRC0805F3400TS"))
    )
    (comp (ref "U17")
      (value "340Ω")
      (footprint "easyedapro:R0805")
      (description "电阻类型:厚膜电阻;阻值:340Ω;精度:±1%;功率:125mW;温度系数:±100ppm/°C;")
      (fields (field (name "Manufacturer Part") "FRC0805F3400TS") (field (name "Manufacturer") "FOJAN(富捷)"))
      (libsource (lib "easyedapro") (part "FRC0805F3400TS"))
    )
    (comp (ref "U18")
      (value "B1205S-1WR3")
      (footprint "easyedapro:PWRM-TH_BXXXXS-1WR3")
      (description "尺寸：11.6*10*6mm 保护方式：短路保护（可持续自恢复）")
      (fields (field (name "Manufacturer") "ZOEYGO(中逸光)"))
      (libsource (lib "easyedapro") (part "B1205S-1WR3_C5264430"))
    )
    (comp (ref "U19")
      (value "AMS1117-ADJ")
      (footprint "easyedapro:SOT-223_L6.7-W3.5-P2.30-BR")
      (description "输出类型:可调;工作电压:18V;输出电压:1.25V~10V;输出电流:1A;电源纹波抑制比(PSRR):60dB@(120Hz);输出极性:正极;")
      (fields (field (name "Manufacturer") "UMW(友台半导体)"))
      (libsource (lib "easyedapro") (part "AMS1117-ADJ_C347224"))
    )
    (comp (ref "U20")
      (value "AMS1117-ADJ")
      (footprint "easyedapro:SOT-223_L6.7-W3.5-P2.30-BR")
      (description "输出类型:可调;工作电压:18V;输出电压:1.25V~10V;输出电流:1A;电源纹波抑制比(PSRR):60dB@(120Hz);输出极性:正极;")
      (fields (field (name "Manufacturer") "UMW(友台半导体)"))
      (libsource (lib "easyedapro") (part "AMS1117-ADJ_C347224"))
    )
    (comp (ref "U21")
      (value "B1205S-1WR3")
      (footprint "easyedapro:PWRM-TH_BXXXXS-1WR3")
      (description "尺寸：11.6*10*6mm 保护方式：短路保护（可持续自恢复）")
      (fields (field (name "Manufacturer") "ZOEYGO(中逸光)"))
      (libsource (lib "easyedapro") (part "B1205S-1WR3_C5264430"))
    )
    (comp (ref "U22")
      (value "340Ω")
      (footprint "easyedapro:R0805")
      (description "电阻类型:厚膜电阻;阻值:340Ω;精度:±1%;功率:125mW;温度系数:±100ppm/°C;")
      (fields (field (name "Manufacturer Part") "FRC0805F3400TS") (field (name "Manufacturer") "FOJAN(富捷)"))
      (libsource (lib "easyedapro") (part "FRC0805F3400TS"))
    )
    (comp (ref "U23")
      (value "340Ω")
      (footprint "easyedapro:R0805")
      (description "电阻类型:厚膜电阻;阻值:340Ω;精度:±1%;功率:125mW;温度系数:±100ppm/°C;")
      (fields (field (name "Manufacturer Part") "FRC0805F3400TS") (field (name "Manufacturer") "FOJAN(富捷)"))
      (libsource (lib "easyedapro") (part "FRC0805F3400TS"))
    )
    (comp (ref "U24")
      (value "B1205S-1WR3")
      (footprint "easyedapro:PWRM-TH_BXXXXS-1WR3")
      (description "尺寸：11.6*10*6mm 保护方式：短路保护（可持续自恢复）")
      (fields (field (name "Manufacturer") "ZOEYGO(中逸光)"))
      (libsource (lib "easyedapro") (part "B1205S-1WR3_C5264430"))
    )
    (comp (ref "U25")
      (value "AMS1117-ADJ")
      (footprint "easyedapro:SOT-223_L6.7-W3.5-P2.30-BR")
      (description "输出类型:可调;工作电压:18V;输出电压:1.25V~10V;输出电流:1A;电源纹波抑制比(PSRR):60dB@(120Hz);输出极性:正极;")
      (fields (field (name "Manufacturer") "UMW(友台半导体)"))
      (libsource (lib "easyedapro") (part "AMS1117-ADJ_C347224"))
    )
    (comp (ref "U26")
      (value "AMS1117-ADJ")
      (footprint "easyedapro:SOT-223_L6.7-W3.5-P2.30-BR")
      (description "输出类型:可调;工作电压:18V;输出电压:1.25V~10V;输出电流:1A;电源纹波抑制比(PSRR):60dB@(120Hz);输出极性:正极;")
      (fields (field (name "Manufacturer") "UMW(友台半导体)"))
      (libsource (lib "easyedapro") (part "AMS1117-ADJ_C347224"))
    )
    (comp (ref "U27")
      (value "B1205S-1WR3")
      (footprint "easyedapro:PWRM-TH_BXXXXS-1WR3")
      (description "尺寸：11.6*10*6mm 保护方式：短路保护（可持续自恢复）")
      (fields (field (name "Manufacturer") "ZOEYGO(中逸光)"))
      (libsource (lib "easyedapro") (part "B1205S-1WR3_C5264430"))
    )
    (comp (ref "U28")
      (value "340Ω")
      (footprint "easyedapro:R0805")
      (description "电阻类型:厚膜电阻;阻值:340Ω;精度:±1%;功率:125mW;温度系数:±100ppm/°C;")
      (fields (field (name "Manufacturer Part") "FRC0805F3400TS") (field (name "Manufacturer") "FOJAN(富捷)"))
      (libsource (lib "easyedapro") (part "FRC0805F3400TS"))
    )
    (comp (ref "U29")
      (value "340Ω")
      (footprint "easyedapro:R0805")
      (description "电阻类型:厚膜电阻;阻值:340Ω;精度:±1%;功率:125mW;温度系数:±100ppm/°C;")
      (fields (field (name "Manufacturer Part") "FRC0805F3400TS") (field (name "Manufacturer") "FOJAN(富捷)"))
      (libsource (lib "easyedapro") (part "FRC0805F3400TS"))
    )
    (comp (ref "U30")
      (value "B1205S-1WR3")
      (footprint "easyedapro:PWRM-TH_BXXXXS-1WR3")
      (description "尺寸：11.6*10*6mm 保护方式：短路保护（可持续自恢复）")
      (fields (field (name "Manufacturer") "ZOEYGO(中逸光)"))
      (libsource (lib "easyedapro") (part "B1205S-1WR3_C5264430"))
    )
    (comp (ref "U31")
      (value "AMS1117-ADJ")
      (footprint "easyedapro:SOT-223_L6.7-W3.5-P2.30-BR")
      (description "输出类型:可调;工作电压:18V;输出电压:1.25V~10V;输出电流:1A;电源纹波抑制比(PSRR):60dB@(120Hz);输出极性:正极;")
      (fields (field (name "Manufacturer") "UMW(友台半导体)"))
      (libsource (lib "easyedapro") (part "AMS1117-ADJ_C347224"))
    )
    (comp (ref "U32")
      (value "AMS1117-ADJ")
      (footprint "easyedapro:SOT-223_L6.7-W3.5-P2.30-BR")
      (description "输出类型:可调;工作电压:18V;输出电压:1.25V~10V;输出电流:1A;电源纹波抑制比(PSRR):60dB@(120Hz);输出极性:正极;")
      (fields (field (name "Manufacturer") "UMW(友台半导体)"))
      (libsource (lib "easyedapro") (part "AMS1117-ADJ_C347224"))
    )
    (comp (ref "U33")
      (value "B1205S-1WR3")
      (footprint "easyedapro:PWRM-TH_BXXXXS-1WR3")
      (description "尺寸：11.6*10*6mm 保护方式：短路保护（可持续自恢复）")
      (fields (field (name "Manufacturer") "ZOEYGO(中逸光)"))
      (libsource (lib "easyedapro") (part "B1205S-1WR3_C5264430"))
    )
    (comp (ref "U34")
      (value "340Ω")
      (footprint "easyedapro:R0805")
      (description "电阻类型:厚膜电阻;阻值:340Ω;精度:±1%;功率:125mW;温度系数:±100ppm/°C;")
      (fields (field (name "Manufacturer Part") "FRC0805F3400TS") (field (name "Manufacturer") "FOJAN(富捷)"))
      (libsource (lib "easyedapro") (part "FRC0805F3400TS"))
    )
    (comp (ref "U35")
      (value "340Ω")
      (footprint "easyedapro:R0805")
      (description "电阻类型:厚膜电阻;阻值:340Ω;精度:±1%;功率:125mW;温度系数:±100ppm/°C;")
      (fields (field (name "Manufacturer Part") "FRC0805F3400TS") (field (name "Manufacturer") "FOJAN(富捷)"))
      (libsource (lib "easyedapro") (part "FRC0805F3400TS"))
    )
    (comp (ref "U36")
      (value "B1205S-1WR3")
      (footprint "easyedapro:PWRM-TH_BXXXXS-1WR3")
      (description "尺寸：11.6*10*6mm 保护方式：短路保护（可持续自恢复）")
      (fields (field (name "Manufacturer") "ZOEYGO(中逸光)"))
      (libsource (lib "easyedapro") (part "B1205S-1WR3_C5264430"))
    )
    (comp (ref "U37")
      (value "AMS1117-ADJ")
      (footprint "easyedapro:SOT-223_L6.7-W3.5-P2.30-BR")
      (description "输出类型:可调;工作电压:18V;输出电压:1.25V~10V;输出电流:1A;电源纹波抑制比(PSRR):60dB@(120Hz);输出极性:正极;")
      (fields (field (name "Manufacturer") "UMW(友台半导体)"))
      (libsource (lib "easyedapro") (part "AMS1117-ADJ_C347224"))
    )
    (comp (ref "U38")
      (value "AMS1117-ADJ")
      (footprint "easyedapro:SOT-223_L6.7-W3.5-P2.30-BR")
      (description "输出类型:可调;工作电压:18V;输出电压:1.25V~10V;输出电流:1A;电源纹波抑制比(PSRR):60dB@(120Hz);输出极性:正极;")
      (fields (field (name "Manufacturer") "UMW(友台半导体)"))
      (libsource (lib "easyedapro") (part "AMS1117-ADJ_C347224"))
    )
    (comp (ref "U39")
      (value "B1205S-1WR3")
      (footprint "easyedapro:PWRM-TH_BXXXXS-1WR3")
      (description "尺寸：11.6*10*6mm 保护方式：短路保护（可持续自恢复）")
      (fields (field (name "Manufacturer") "ZOEYGO(中逸光)"))
      (libsource (lib "easyedapro") (part "B1205S-1WR3_C5264430"))
    )
    (comp (ref "U40")
      (value "340Ω")
      (footprint "easyedapro:R0805")
      (description "电阻类型:厚膜电阻;阻值:340Ω;精度:±1%;功率:125mW;温度系数:±100ppm/°C;")
      (fields (field (name "Manufacturer Part") "FRC0805F3400TS") (field (name "Manufacturer") "FOJAN(富捷)"))
      (libsource (lib "easyedapro") (part "FRC0805F3400TS"))
    )
    (comp (ref "U41")
      (value "340Ω")
      (footprint "easyedapro:R0805")
      (description "电阻类型:厚膜电阻;阻值:340Ω;精度:±1%;功率:125mW;温度系数:±100ppm/°C;")
      (fields (field (name "Manufacturer Part") "FRC0805F3400TS") (field (name "Manufacturer") "FOJAN(富捷)"))
      (libsource (lib "easyedapro") (part "FRC0805F3400TS"))
    )
    (comp (ref "U42")
      (value "B1205S-1WR3")
      (footprint "easyedapro:PWRM-TH_BXXXXS-1WR3")
      (description "尺寸：11.6*10*6mm 保护方式：短路保护（可持续自恢复）")
      (fields (field (name "Manufacturer") "ZOEYGO(中逸光)"))
      (libsource (lib "easyedapro") (part "B1205S-1WR3_C5264430"))
    )
    (comp (ref "U43")
      (value "AMS1117-ADJ")
      (footprint "easyedapro:SOT-223_L6.7-W3.5-P2.30-BR")
      (description "输出类型:可调;工作电压:18V;输出电压:1.25V~10V;输出电流:1A;电源纹波抑制比(PSRR):60dB@(120Hz);输出极性:正极;")
      (fields (field (name "Manufacturer") "UMW(友台半导体)"))
      (libsource (lib "easyedapro") (part "AMS1117-ADJ_C347224"))
    )
    (comp (ref "U44")
      (value "AMS1117-ADJ")
      (footprint "easyedapro:SOT-223_L6.7-W3.5-P2.30-BR")
      (description "输出类型:可调;工作电压:18V;输出电压:1.25V~10V;输出电流:1A;电源纹波抑制比(PSRR):60dB@(120Hz);输出极性:正极;")
      (fields (field (name "Manufacturer") "UMW(友台半导体)"))
      (libsource (lib "easyedapro") (part "AMS1117-ADJ_C347224"))
    )
    (comp (ref "U45")
      (value "B1205S-1WR3")
      (footprint "easyedapro:PWRM-TH_BXXXXS-1WR3")
      (description "尺寸：11.6*10*6mm 保护方式：短路保护（可持续自恢复）")
      (fields (field (name "Manufacturer") "ZOEYGO(中逸光)"))
      (libsource (lib "easyedapro") (part "B1205S-1WR3_C5264430"))
    )
    (comp (ref "U46")
      (value "340Ω")
      (footprint "easyedapro:R0805")
      (description "电阻类型:厚膜电阻;阻值:340Ω;精度:±1%;功率:125mW;温度系数:±100ppm/°C;")
      (fields (field (name "Manufacturer Part") "FRC0805F3400TS") (field (name "Manufacturer") "FOJAN(富捷)"))
      (libsource (lib "easyedapro") (part "FRC0805F3400TS"))
    )
  )
  (nets
    (net (code "1") (name "/3+") (class "Default")
      (node (ref "C65") (pin "1") (pinfunction "1_1") (pintype "unspecified"))
      (node (ref "C66") (pin "1") (pinfunction "1_1") (pintype "unspecified"))
      (node (ref "C69") (pin "2") (pinfunction "2_2") (pintype "unspecified"))
      (node (ref "P3") (pin "2") (pinfunction "2_2") (pintype "unspecified"))
      (node (ref "R4") (pin "1") (pinfunction "1_1") (pintype "unspecified"))
      (node (ref "R4") (pin "2") (pinfunction "2_2") (pintype "unspecified"))
      (node (ref "U10") (pin "2") (pinfunction "2_2") (pintype "unspecified"))
      (node (ref "U6") (pin "3") (pinfunction "-VO_3") (pintype "unspecified"))
      (node (ref "U8") (pin "2") (pinfunction "VOUT(TAB)_2") (pintype "unspecified"))
    )
    (net (code "2") (name "/4+") (class "Default")
      (node (ref "C68") (pin "1") (pinfunction "1_1") (pintype "unspecified"))
      (node (ref "C69") (pin "1") (pinfunction "1_1") (pintype "unspecified"))
      (node (ref "C72") (pin "2") (pinfunction "2_2") (pintype "unspecified"))
      (node (ref "P3") (pin "1") (pinfunction "1_1") (pintype "unspecified"))
      (node (ref "R6") (pin "1") (pinfunction "1_1") (pintype "unspecified"))
      (node (ref "R6") (pin "2") (pinfunction "2_2") (pintype "unspecified"))
      (node (ref "U11") (pin "2") (pinfunction "2_2") (pintype "unspecified"))
      (node (ref "U13") (pin "2") (pinfunction "VOUT(TAB)_2") (pintype "unspecified"))
      (node (ref "U9") (pin "3") (pinfunction "-VO_3") (pintype "unspecified"))
    )
    (net (code "3") (name "/5+") (class "Default")
      (node (ref "C71") (pin "1") (pinfunction "1_1") (pintype "unspecified"))
      (node (ref "C72") (pin "1") (pinfunction "1_1") (pintype "unspecified"))
      (node (ref "C75") (pin "2") (pinfunction "2_2") (pintype "unspecified"))
      (node (ref "P4") (pin "2") (pinfunction "2_2") (pintype "unspecified"))
      (node (ref "R7") (pin "1") (pinfunction "1_1") (pintype "unspecified"))
      (node (ref "R7") (pin "2") (pinfunction "2_2") (pintype "unspecified"))
      (node (ref "U12") (pin "3") (pinfunction "-VO_3") (pintype "unspecified"))
      (node (ref "U14") (pin "2") (pinfunction "VOUT(TAB)_2") (pintype "unspecified"))
      (node (ref "U16") (pin "2") (pinfunction "2_2") (pintype "unspecified"))
    )
    (net (code "4") (name "/6+") (class "Default")
      (node (ref "C74") (pin "1") (pinfunction "1_1") (pintype "unspecified"))
      (node (ref "C75") (pin "1") (pinfunction "1_1") (pintype "unspecified"))
      (node (ref "C78") (pin "2") (pinfunction "2_2") (pintype "unspecified"))
      (node (ref "P4") (pin "1") (pinfunction "1_1") (pintype "unspecified"))
      (node (ref "R10") (pin "1") (pinfunction "1_1") (pintype "unspecified"))
      (node (ref "R10") (pin "2") (pinfunction "2_2") (pintype "unspecified"))
      (node (ref "U15") (pin "3") (pinfunction "-VO_3") (pintype "unspecified"))
      (node (ref "U17") (pin "2") (pinfunction "2_2") (pintype "unspecified"))
      (node (ref "U19") (pin "2") (pinfunction "VOUT(TAB)_2") (pintype "unspecified"))
    )
    (net (code "5") (name "/7+") (class "Default")
      (node (ref "C77") (pin "1") (pinfunction "1_1") (pintype "unspecified"))
      (node (ref "C78") (pin "1") (pinfunction "1_1") (pintype "unspecified"))
      (node (ref "C81") (pin "2") (pinfunction "2_2") (pintype "unspecified"))
      (node (ref "P5") (pin "2") (pinfunction "2_2") (pintype "unspecified"))
      (node (ref "R11") (pin "1") (pinfunction "1_1") (pintype "unspecified"))
      (node (ref "R11") (pin "2") (pinfunction "2_2") (pintype "unspecified"))
      (node (ref "U18") (pin "3") (pinfunction "-VO_3") (pintype "unspecified"))
      (node (ref "U20") (pin "2") (pinfunction "VOUT(TAB)_2") (pintype "unspecified"))
      (node (ref "U22") (pin "2") (pinfunction "2_2") (pintype "unspecified"))
    )
    (net (code "6") (name "/8+") (class "Default")
      (node (ref "C80") (pin "1") (pinfunction "1_1") (pintype "unspecified"))
      (node (ref "C81") (pin "1") (pinfunction "1_1") (pintype "unspecified"))
      (node (ref "C84") (pin "2") (pinfunction "2_2") (pintype "unspecified"))
      (node (ref "P5") (pin "1") (pinfunction "1_1") (pintype "unspecified"))
      (node (ref "R14") (pin "1") (pinfunction "1_1") (pintype "unspecified"))
      (node (ref "R14") (pin "2") (pinfunction "2_2") (pintype "unspecified"))
      (node (ref "U21") (pin "3") (pinfunction "-VO_3") (pintype "unspecified"))
      (node (ref "U23") (pin "2") (pinfunction "2_2") (pintype "unspecified"))
      (node (ref "U25") (pin "2") (pinfunction "VOUT(TAB)_2") (pintype "unspecified"))
    )
    (net (code "7") (name "/9+") (class "Default")
      (node (ref "C83") (pin "1") (pinfunction "1_1") (pintype "unspecified"))
      (node (ref "C84") (pin "1") (pinfunction "1_1") (pintype "unspecified"))
      (node (ref "C87") (pin "2") (pinfunction "2_2") (pintype "unspecified"))
      (node (ref "P6") (pin "2") (pinfunction "2_2") (pintype "unspecified"))
      (node (ref "R15") (pin "1") (pinfunction "1_1") (pintype "unspecified"))
      (node (ref "R15") (pin "2") (pinfunction "2_2") (pintype "unspecified"))
      (node (ref "U24") (pin "3") (pinfunction "-VO_3") (pintype "unspecified"))
      (node (ref "U26") (pin "2") (pinfunction "VOUT(TAB)_2") (pintype "unspecified"))
      (node (ref "U28") (pin "2") (pinfunction "2_2") (pintype "unspecified"))
    )
    (net (code "8") (name "/10+") (class "Default")
      (node (ref "C86") (pin "1") (pinfunction "1_1") (pintype "unspecified"))
      (node (ref "C87") (pin "1") (pinfunction "1_1") (pintype "unspecified"))
      (node (ref "C90") (pin "2") (pinfunction "2_2") (pintype "unspecified"))
      (node (ref "P6") (pin "1") (pinfunction "1_1") (pintype "unspecified"))
      (node (ref "R18") (pin "1") (pinfunction "1_1") (pintype "unspecified"))
      (node (ref "R18") (pin "2") (pinfunction "2_2") (pintype "unspecified"))
      (node (ref "U27") (pin "3") (pinfunction "-VO_3") (pintype "unspecified"))
      (node (ref "U29") (pin "2") (pinfunction "2_2") (pintype "unspecified"))
      (node (ref "U31") (pin "2") (pinfunction "VOUT(TAB)_2") (pintype "unspecified"))
    )
    (net (code "9") (name "/11+") (class "Default")
      (node (ref "C89") (pin "1") (pinfunction "1_1") (pintype "unspecified"))
      (node (ref "C90") (pin "1") (pinfunction "1_1") (pintype "unspecified"))
      (node (ref "C93") (pin "2") (pinfunction "2_2") (pintype "unspecified"))
      (node (ref "P7") (pin "2") (pinfunction "2_2") (pintype "unspecified"))
      (node (ref "R19") (pin "1") (pinfunction "1_1") (pintype "unspecified"))
      (node (ref "R19") (pin "2") (pinfunction "2_2") (pintype "unspecified"))
      (node (ref "U30") (pin "3") (pinfunction "-VO_3") (pintype "unspecified"))
      (node (ref "U32") (pin "2") (pinfunction "VOUT(TAB)_2") (pintype "unspecified"))
      (node (ref "U34") (pin "2") (pinfunction "2_2") (pintype "unspecified"))
    )
    (net (code "10") (name "/12+") (class "Default")
      (node (ref "C92") (pin "1") (pinfunction "1_1") (pintype "unspecified"))
      (node (ref "C93") (pin "1") (pinfunction "1_1") (pintype "unspecified"))
      (node (ref "C96") (pin "2") (pinfunction "2_2") (pintype "unspecified"))
      (node (ref "P7") (pin "1") (pinfunction "1_1") (pintype "unspecified"))
      (node (ref "R22") (pin "1") (pinfunction "1_1") (pintype "unspecified"))
      (node (ref "R22") (pin "2") (pinfunction "2_2") (pintype "unspecified"))
      (node (ref "U33") (pin "3") (pinfunction "-VO_3") (pintype "unspecified"))
      (node (ref "U35") (pin "2") (pinfunction "2_2") (pintype "unspecified"))
      (node (ref "U37") (pin "2") (pinfunction "VOUT(TAB)_2") (pintype "unspecified"))
    )
    (net (code "11") (name "/13+") (class "Default")
      (node (ref "C95") (pin "1") (pinfunction "1_1") (pintype "unspecified"))
      (node (ref "C96") (pin "1") (pinfunction "1_1") (pintype "unspecified"))
      (node (ref "C99") (pin "2") (pinfunction "2_2") (pintype "unspecified"))
      (node (ref "P8") (pin "2") (pinfunction "2_2") (pintype "unspecified"))
      (node (ref "R23") (pin "1") (pinfunction "1_1") (pintype "unspecified"))
      (node (ref "R23") (pin "2") (pinfunction "2_2") (pintype "unspecified"))
      (node (ref "U36") (pin "3") (pinfunction "-VO_3") (pintype "unspecified"))
      (node (ref "U38") (pin "2") (pinfunction "VOUT(TAB)_2") (pintype "unspecified"))
      (node (ref "U40") (pin "2") (pinfunction "2_2") (pintype "unspecified"))
    )
    (net (code "12") (name "/14+") (class "Default")
      (node (ref "C102") (pin "2") (pinfunction "2_2") (pintype "unspecified"))
      (node (ref "C98") (pin "1") (pinfunction "1_1") (pintype "unspecified"))
      (node (ref "C99") (pin "1") (pinfunction "1_1") (pintype "unspecified"))
      (node (ref "P8") (pin "1") (pinfunction "1_1") (pintype "unspecified"))
      (node (ref "R26") (pin "1") (pinfunction "1_1") (pintype "unspecified"))
      (node (ref "R26") (pin "2") (pinfunction "2_2") (pintype "unspecified"))
      (node (ref "U39") (pin "3") (pinfunction "-VO_3") (pintype "unspecified"))
      (node (ref "U41") (pin "2") (pinfunction "2_2") (pintype "unspecified"))
      (node (ref "U43") (pin "2") (pinfunction "VOUT(TAB)_2") (pintype "unspecified"))
    )
    (net (code "13") (name "/15+") (class "Default")
      (node (ref "C101") (pin "1") (pinfunction "1_1") (pintype "unspecified"))
      (node (ref "C102") (pin "1") (pinfunction "1_1") (pintype "unspecified"))
      (node (ref "C105") (pin "2") (pinfunction "2_2") (pintype "unspecified"))
      (node (ref "P9") (pin "2") (pinfunction "2_2") (pintype "unspecified"))
      (node (ref "R27") (pin "1") (pinfunction "1_1") (pintype "unspecified"))
      (node (ref "R27") (pin "2") (pinfunction "2_2") (pintype "unspecified"))
      (node (ref "U42") (pin "3") (pinfunction "-VO_3") (pintype "unspecified"))
      (node (ref "U44") (pin "2") (pinfunction "VOUT(TAB)_2") (pintype "unspecified"))
      (node (ref "U46") (pin "2") (pinfunction "2_2") (pintype "unspecified"))
    )
    (net (code "14") (name "/15-") (class "Default")
      (node (ref "C104") (pin "1") (pinfunction "1_1") (pintype "unspecified"))
      (node (ref "C105") (pin "1") (pinfunction "1_1") (pintype "unspecified"))
      (node (ref "P9") (pin "1") (pinfunction "1_1") (pintype "unspecified"))
      (node (ref "R30") (pin "1") (pinfunction "1_1") (pintype "unspecified"))
      (node (ref "R30") (pin "2") (pinfunction "2_2") (pintype "unspecified"))
      (node (ref "U45") (pin "3") (pinfunction "-VO_3") (pintype "unspecified"))
    )
    (net (code "15") (name "/CELL1+") (class "Default")
      (node (ref "C63") (pin "2") (pinfunction "2_2") (pintype "unspecified"))
      (node (ref "P2") (pin "2") (pinfunction "2_2") (pintype "unspecified"))
      (node (ref "U2") (pin "2") (pinfunction "VOUT(TAB)_2") (pintype "unspecified"))
      (node (ref "U4") (pin "2") (pinfunction "2_2") (pintype "unspecified"))
    )
    (net (code "16") (name "/CELL2+") (class "Default")
      (node (ref "C62") (pin "1") (pinfunction "1_1") (pintype "unspecified"))
      (node (ref "C63") (pin "1") (pinfunction "1_1") (pintype "unspecified"))
      (node (ref "C66") (pin "2") (pinfunction "2_2") (pintype "unspecified"))
      (node (ref "P2") (pin "1") (pinfunction "1_1") (pintype "unspecified"))
      (node (ref "R2") (pin "1") (pinfunction "1_1") (pintype "unspecified"))
      (node (ref "R2") (pin "2") (pinfunction "2_2") (pintype "unspecified"))
      (node (ref "U3") (pin "3") (pinfunction "-VO_3") (pintype "unspecified"))
      (node (ref "U5") (pin "2") (pinfunction "VOUT(TAB)_2") (pintype "unspecified"))
      (node (ref "U7") (pin "2") (pinfunction "2_2") (pintype "unspecified"))
    )
    (net (code "17") (name "12V") (class "Default")
      (node (ref "C100") (pin "2") (pinfunction "2_2") (pintype "unspecified"))
      (node (ref "C103") (pin "2") (pinfunction "2_2") (pintype "unspecified"))
      (node (ref "C61") (pin "2") (pinfunction "2_2") (pintype "unspecified"))
      (node (ref "C64") (pin "2") (pinfunction "2_2") (pintype "unspecified"))
      (node (ref "C67") (pin "2") (pinfunction "2_2") (pintype "unspecified"))
      (node (ref "C70") (pin "2") (pinfunction "2_2") (pintype "unspecified"))
      (node (ref "C73") (pin "2") (pinfunction "2_2") (pintype "unspecified"))
      (node (ref "C76") (pin "2") (pinfunction "2_2") (pintype "unspecified"))
      (node (ref "C79") (pin "2") (pinfunction "2_2") (pintype "unspecified"))
      (node (ref "C82") (pin "2") (pinfunction "2_2") (pintype "unspecified"))
      (node (ref "C85") (pin "2") (pinfunction "2_2") (pintype "unspecified"))
      (node (ref "C88") (pin "2") (pinfunction "2_2") (pintype "unspecified"))
      (node (ref "C91") (pin "2") (pinfunction "2_2") (pintype "unspecified"))
      (node (ref "C94") (pin "2") (pinfunction "2_2") (pintype "unspecified"))
      (node (ref "C97") (pin "2") (pinfunction "2_2") (pintype "unspecified"))
      (node (ref "D1") (pin "1") (pinfunction "K_1") (pintype "unspecified"))
      (node (ref "Q1") (pin "2") (pinfunction "S_2") (pintype "unspecified"))
      (node (ref "U12") (pin "2") (pinfunction "+VIN_2") (pintype "unspecified"))
      (node (ref "U15") (pin "2") (pinfunction "+VIN_2") (pintype "unspecified"))
      (node (ref "U18") (pin "2") (pinfunction "+VIN_2") (pintype "unspecified"))
      (node (ref "U21") (pin "2") (pinfunction "+VIN_2") (pintype "unspecified"))
      (node (ref "U24") (pin "2") (pinfunction "+VIN_2") (pintype "unspecified"))
      (node (ref "U27") (pin "2") (pinfunction "+VIN_2") (pintype "unspecified"))
      (node (ref "U3") (pin "2") (pinfunction "+VIN_2") (pintype "unspecified"))
      (node (ref "U30") (pin "2") (pinfunction "+VIN_2") (pintype "unspecified"))
      (node (ref "U33") (pin "2") (pinfunction "+VIN_2") (pintype "unspecified"))
      (node (ref "U36") (pin "2") (pinfunction "+VIN_2") (pintype "unspecified"))
      (node (ref "U39") (pin "2") (pinfunction "+VIN_2") (pintype "unspecified"))
      (node (ref "U42") (pin "2") (pinfunction "+VIN_2") (pintype "unspecified"))
      (node (ref "U45") (pin "2") (pinfunction "+VIN_2") (pintype "unspecified"))
      (node (ref "U6") (pin "2") (pinfunction "+VIN_2") (pintype "unspecified"))
      (node (ref "U9") (pin "2") (pinfunction "+VIN_2") (pintype "unspecified"))
    )
    (net (code "18") (name "GND") (class "Default")
      (node (ref "C100") (pin "1") (pinfunction "1_1") (pintype "unspecified"))
      (node (ref "C103") (pin "1") (pinfunction "1_1") (pintype "unspecified"))
      (node (ref "C61") (pin "1") (pinfunction "1_1") (pintype "unspecified"))
      (node (ref "C64") (pin "1") (pinfunction "1_1") (pintype "unspecified"))
      (node (ref "C67") (pin "1") (pinfunction "1_1") (pintype "unspecified"))
      (node (ref "C70") (pin "1") (pinfunction "1_1") (pintype "unspecified"))
      (node (ref "C73") (pin "1") (pinfunction "1_1") (pintype "unspecified"))
      (node (ref "C76") (pin "1") (pinfunction "1_1") (pintype "unspecified"))
      (node (ref "C79") (pin "1") (pinfunction "1_1") (pintype "unspecified"))
      (node (ref "C82") (pin "1") (pinfunction "1_1") (pintype "unspecified"))
      (node (ref "C85") (pin "1") (pinfunction "1_1") (pintype "unspecified"))
      (node (ref "C88") (pin "1") (pinfunction "1_1") (pintype "unspecified"))
      (node (ref "C91") (pin "1") (pinfunction "1_1") (pintype "unspecified"))
      (node (ref "C94") (pin "1") (pinfunction "1_1") (pintype "unspecified"))
      (node (ref "C97") (pin "1") (pinfunction "1_1") (pintype "unspecified"))
      (node (ref "P1") (pin "2") (pinfunction "2_2") (pintype "unspecified"))
      (node (ref "R32") (pin "1") (pinfunction "1_1") (pintype "input"))
      (node (ref "U12") (pin "1") (pinfunction "GND_1") (pintype "unspecified"))
      (node (ref "U15") (pin "1") (pinfunction "GND_1") (pintype "unspecified"))
      (node (ref "U18") (pin "1") (pinfunction "GND_1") (pintype "unspecified"))
      (node (ref "U21") (pin "1") (pinfunction "GND_1") (pintype "unspecified"))
      (node (ref "U24") (pin "1") (pinfunction "GND_1") (pintype "unspecified"))
      (node (ref "U27") (pin "1") (pinfunction "GND_1") (pintype "unspecified"))
      (node (ref "U3") (pin "1") (pinfunction "GND_1") (pintype "unspecified"))
      (node (ref "U30") (pin "1") (pinfunction "GND_1") (pintype "unspecified"))
      (node (ref "U33") (pin "1") (pinfunction "GND_1") (pintype "unspecified"))
      (node (ref "U36") (pin "1") (pinfunction "GND_1") (pintype "unspecified"))
      (node (ref "U39") (pin "1") (pinfunction "GND_1") (pintype "unspecified"))
      (node (ref "U42") (pin "1") (pinfunction "GND_1") (pintype "unspecified"))
      (node (ref "U45") (pin "1") (pinfunction "GND_1") (pintype "unspecified"))
      (node (ref "U6") (pin "1") (pinfunction "GND_1") (pintype "unspecified"))
      (node (ref "U9") (pin "1") (pinfunction "GND_1") (pintype "unspecified"))
    )
    (net (code "19") (name "Net-(D1-A)") (class "Default")
      (node (ref "D1") (pin "2") (pinfunction "A_2") (pintype "unspecified"))
      (node (ref "R31") (pin "1") (pinfunction "1_1") (pintype "input"))
      (node (ref "R32") (pin "2") (pinfunction "2_2") (pintype "input"))
    )
    (net (code "20") (name "Net-(Q1-D)") (class "Default")
      (node (ref "P1") (pin "1") (pinfunction "1_1") (pintype "unspecified"))
      (node (ref "Q1") (pin "3") (pinfunction "D_3") (pintype "unspecified"))
    )
    (net (code "21") (name "Net-(Q1-G)") (class "Default")
      (node (ref "Q1") (pin "1") (pinfunction "G_1") (pintype "unspecified"))
      (node (ref "R31") (pin "2") (pinfunction "2_2") (pintype "input"))
    )
    (net (code "22") (name "Net-(U2-ADJ(GND))") (class "Default")
      (node (ref "R2") (pin "3") (pinfunction "3_3") (pintype "unspecified"))
      (node (ref "U2") (pin "1") (pinfunction "ADJ(GND)_1") (pintype "unspecified"))
      (node (ref "U4") (pin "1") (pinfunction "1_1") (pintype "unspecified"))
    )
    (net (code "23") (name "Net-(U2-VIN)") (class "Default")
      (node (ref "C62") (pin "2") (pinfunction "2_2") (pintype "unspecified"))
      (node (ref "R1") (pin "2") (pinfunction "2_2") (pintype "input"))
      (node (ref "U2") (pin "3") (pinfunction "VIN_3") (pintype "unspecified"))
    )
    (net (code "24") (name "Net-(U3-+VO)") (class "Default")
      (node (ref "R1") (pin "1") (pinfunction "1_1") (pintype "input"))
      (node (ref "U3") (pin "4") (pinfunction "+VO_4") (pintype "unspecified"))
    )
    (net (code "25") (name "Net-(U5-ADJ(GND))") (class "Default")
      (node (ref "R4") (pin "3") (pinfunction "3_3") (pintype "unspecified"))
      (node (ref "U5") (pin "1") (pinfunction "ADJ(GND)_1") (pintype "unspecified"))
      (node (ref "U7") (pin "1") (pinfunction "1_1") (pintype "unspecified"))
    )
    (net (code "26") (name "Net-(U5-VIN)") (class "Default")
      (node (ref "C65") (pin "2") (pinfunction "2_2") (pintype "unspecified"))
      (node (ref "R3") (pin "2") (pinfunction "2_2") (pintype "input"))
      (node (ref "U5") (pin "3") (pinfunction "VIN_3") (pintype "unspecified"))
    )
    (net (code "27") (name "Net-(U6-+VO)") (class "Default")
      (node (ref "R3") (pin "1") (pinfunction "1_1") (pintype "input"))
      (node (ref "U6") (pin "4") (pinfunction "+VO_4") (pintype "unspecified"))
    )
    (net (code "28") (name "Net-(U8-ADJ(GND))") (class "Default")
      (node (ref "R6") (pin "3") (pinfunction "3_3") (pintype "unspecified"))
      (node (ref "U10") (pin "1") (pinfunction "1_1") (pintype "unspecified"))
      (node (ref "U8") (pin "1") (pinfunction "ADJ(GND)_1") (pintype "unspecified"))
    )
    (net (code "29") (name "Net-(U8-VIN)") (class "Default")
      (node (ref "C68") (pin "2") (pinfunction "2_2") (pintype "unspecified"))
      (node (ref "R5") (pin "2") (pinfunction "2_2") (pintype "input"))
      (node (ref "U8") (pin "3") (pinfunction "VIN_3") (pintype "unspecified"))
    )
    (net (code "30") (name "Net-(U9-+VO)") (class "Default")
      (node (ref "R5") (pin "1") (pinfunction "1_1") (pintype "input"))
      (node (ref "U9") (pin "4") (pinfunction "+VO_4") (pintype "unspecified"))
    )
    (net (code "31") (name "Net-(U12-+VO)") (class "Default")
      (node (ref "R8") (pin "1") (pinfunction "1_1") (pintype "input"))
      (node (ref "U12") (pin "4") (pinfunction "+VO_4") (pintype "unspecified"))
    )
    (net (code "32") (name "Net-(U13-ADJ(GND))") (class "Default")
      (node (ref "R7") (pin "3") (pinfunction "3_3") (pintype "unspecified"))
      (node (ref "U11") (pin "1") (pinfunction "1_1") (pintype "unspecified"))
      (node (ref "U13") (pin "1") (pinfunction "ADJ(GND)_1") (pintype "unspecified"))
    )
    (net (code "33") (name "Net-(U13-VIN)") (class "Default")
      (node (ref "C71") (pin "2") (pinfunction "2_2") (pintype "unspecified"))
      (node (ref "R8") (pin "2") (pinfunction "2_2") (pintype "input"))
      (node (ref "U13") (pin "3") (pinfunction "VIN_3") (pintype "unspecified"))
    )
    (net (code "34") (name "Net-(U14-ADJ(GND))") (class "Default")
      (node (ref "R10") (pin "3") (pinfunction "3_3") (pintype "unspecified"))
      (node (ref "U14") (pin "1") (pinfunction "ADJ(GND)_1") (pintype "unspecified"))
      (node (ref "U16") (pin "1") (pinfunction "1_1") (pintype "unspecified"))
    )
    (net (code "35") (name "Net-(U14-VIN)") (class "Default")
      (node (ref "C74") (pin "2") (pinfunction "2_2") (pintype "unspecified"))
      (node (ref "R9") (pin "2") (pinfunction "2_2") (pintype "input"))
      (node (ref "U14") (pin "3") (pinfunction "VIN_3") (pintype "unspecified"))
    )
    (net (code "36") (name "Net-(U15-+VO)") (class "Default")
      (node (ref "R9") (pin "1") (pinfunction "1_1") (pintype "input"))
      (node (ref "U15") (pin "4") (pinfunction "+VO_4") (pintype "unspecified"))
    )
    (net (code "37") (name "Net-(U18-+VO)") (class "Default")
      (node (ref "R12") (pin "1") (pinfunction "1_1") (pintype "input"))
      (node (ref "U18") (pin "4") (pinfunction "+VO_4") (pintype "unspecified"))
    )
    (net (code "38") (name "Net-(U19-ADJ(GND))") (class "Default")
      (node (ref "R11") (pin "3") (pinfunction "3_3") (pintype "unspecified"))
      (node (ref "U17") (pin "1") (pinfunction "1_1") (pintype "unspecified"))
      (node (ref "U19") (pin "1") (pinfunction "ADJ(GND)_1") (pintype "unspecified"))
    )
    (net (code "39") (name "Net-(U19-VIN)") (class "Default")
      (node (ref "C77") (pin "2") (pinfunction "2_2") (pintype "unspecified"))
      (node (ref "R12") (pin "2") (pinfunction "2_2") (pintype "input"))
      (node (ref "U19") (pin "3") (pinfunction "VIN_3") (pintype "unspecified"))
    )
    (net (code "40") (name "Net-(U20-ADJ(GND))") (class "Default")
      (node (ref "R14") (pin "3") (pinfunction "3_3") (pintype "unspecified"))
      (node (ref "U20") (pin "1") (pinfunction "ADJ(GND)_1") (pintype "unspecified"))
      (node (ref "U22") (pin "1") (pinfunction "1_1") (pintype "unspecified"))
    )
    (net (code "41") (name "Net-(U20-VIN)") (class "Default")
      (node (ref "C80") (pin "2") (pinfunction "2_2") (pintype "unspecified"))
      (node (ref "R13") (pin "2") (pinfunction "2_2") (pintype "input"))
      (node (ref "U20") (pin "3") (pinfunction "VIN_3") (pintype "unspecified"))
    )
    (net (code "42") (name "Net-(U21-+VO)") (class "Default")
      (node (ref "R13") (pin "1") (pinfunction "1_1") (pintype "input"))
      (node (ref "U21") (pin "4") (pinfunction "+VO_4") (pintype "unspecified"))
    )
    (net (code "43") (name "Net-(U24-+VO)") (class "Default")
      (node (ref "R16") (pin "1") (pinfunction "1_1") (pintype "input"))
      (node (ref "U24") (pin "4") (pinfunction "+VO_4") (pintype "unspecified"))
    )
    (net (code "44") (name "Net-(U25-ADJ(GND))") (class "Default")
      (node (ref "R15") (pin "3") (pinfunction "3_3") (pintype "unspecified"))
      (node (ref "U23") (pin "1") (pinfunction "1_1") (pintype "unspecified"))
      (node (ref "U25") (pin "1") (pinfunction "ADJ(GND)_1") (pintype "unspecified"))
    )
    (net (code "45") (name "Net-(U25-VIN)") (class "Default")
      (node (ref "C83") (pin "2") (pinfunction "2_2") (pintype "unspecified"))
      (node (ref "R16") (pin "2") (pinfunction "2_2") (pintype "input"))
      (node (ref "U25") (pin "3") (pinfunction "VIN_3") (pintype "unspecified"))
    )
    (net (code "46") (name "Net-(U26-ADJ(GND))") (class "Default")
      (node (ref "R18") (pin "3") (pinfunction "3_3") (pintype "unspecified"))
      (node (ref "U26") (pin "1") (pinfunction "ADJ(GND)_1") (pintype "unspecified"))
      (node (ref "U28") (pin "1") (pinfunction "1_1") (pintype "unspecified"))
    )
    (net (code "47") (name "Net-(U26-VIN)") (class "Default")
      (node (ref "C86") (pin "2") (pinfunction "2_2") (pintype "unspecified"))
      (node (ref "R17") (pin "2") (pinfunction "2_2") (pintype "input"))
      (node (ref "U26") (pin "3") (pinfunction "VIN_3") (pintype "unspecified"))
    )
    (net (code "48") (name "Net-(U27-+VO)") (class "Default")
      (node (ref "R17") (pin "1") (pinfunction "1_1") (pintype "input"))
      (node (ref "U27") (pin "4") (pinfunction "+VO_4") (pintype "unspecified"))
    )
    (net (code "49") (name "Net-(U30-+VO)") (class "Default")
      (node (ref "R20") (pin "1") (pinfunction "1_1") (pintype "input"))
      (node (ref "U30") (pin "4") (pinfunction "+VO_4") (pintype "unspecified"))
    )
    (net (code "50") (name "Net-(U31-ADJ(GND))") (class "Default")
      (node (ref "R19") (pin "3") (pinfunction "3_3") (pintype "unspecified"))
      (node (ref "U29") (pin "1") (pinfunction "1_1") (pintype "unspecified"))
      (node (ref "U31") (pin "1") (pinfunction "ADJ(GND)_1") (pintype "unspecified"))
    )
    (net (code "51") (name "Net-(U31-VIN)") (class "Default")
      (node (ref "C89") (pin "2") (pinfunction "2_2") (pintype "unspecified"))
      (node (ref "R20") (pin "2") (pinfunction "2_2") (pintype "input"))
      (node (ref "U31") (pin "3") (pinfunction "VIN_3") (pintype "unspecified"))
    )
    (net (code "52") (name "Net-(U32-ADJ(GND))") (class "Default")
      (node (ref "R22") (pin "3") (pinfunction "3_3") (pintype "unspecified"))
      (node (ref "U32") (pin "1") (pinfunction "ADJ(GND)_1") (pintype "unspecified"))
      (node (ref "U34") (pin "1") (pinfunction "1_1") (pintype "unspecified"))
    )
    (net (code "53") (name "Net-(U32-VIN)") (class "Default")
      (node (ref "C92") (pin "2") (pinfunction "2_2") (pintype "unspecified"))
      (node (ref "R21") (pin "2") (pinfunction "2_2") (pintype "input"))
      (node (ref "U32") (pin "3") (pinfunction "VIN_3") (pintype "unspecified"))
    )
    (net (code "54") (name "Net-(U33-+VO)") (class "Default")
      (node (ref "R21") (pin "1") (pinfunction "1_1") (pintype "input"))
      (node (ref "U33") (pin "4") (pinfunction "+VO_4") (pintype "unspecified"))
    )
    (net (code "55") (name "Net-(U36-+VO)") (class "Default")
      (node (ref "R24") (pin "1") (pinfunction "1_1") (pintype "input"))
      (node (ref "U36") (pin "4") (pinfunction "+VO_4") (pintype "unspecified"))
    )
    (net (code "56") (name "Net-(U37-ADJ(GND))") (class "Default")
      (node (ref "R23") (pin "3") (pinfunction "3_3") (pintype "unspecified"))
      (node (ref "U35") (pin "1") (pinfunction "1_1") (pintype "unspecified"))
      (node (ref "U37") (pin "1") (pinfunction "ADJ(GND)_1") (pintype "unspecified"))
    )
    (net (code "57") (name "Net-(U37-VIN)") (class "Default")
      (node (ref "C95") (pin "2") (pinfunction "2_2") (pintype "unspecified"))
      (node (ref "R24") (pin "2") (pinfunction "2_2") (pintype "input"))
      (node (ref "U37") (pin "3") (pinfunction "VIN_3") (pintype "unspecified"))
    )
    (net (code "58") (name "Net-(U38-ADJ(GND))") (class "Default")
      (node (ref "R26") (pin "3") (pinfunction "3_3") (pintype "unspecified"))
      (node (ref "U38") (pin "1") (pinfunction "ADJ(GND)_1") (pintype "unspecified"))
      (node (ref "U40") (pin "1") (pinfunction "1_1") (pintype "unspecified"))
    )
    (net (code "59") (name "Net-(U38-VIN)") (class "Default")
      (node (ref "C98") (pin "2") (pinfunction "2_2") (pintype "unspecified"))
      (node (ref "R25") (pin "2") (pinfunction "2_2") (pintype "input"))
      (node (ref "U38") (pin "3") (pinfunction "VIN_3") (pintype "unspecified"))
    )
    (net (code "60") (name "Net-(U39-+VO)") (class "Default")
      (node (ref "R25") (pin "1") (pinfunction "1_1") (pintype "input"))
      (node (ref "U39") (pin "4") (pinfunction "+VO_4") (pintype "unspecified"))
    )
    (net (code "61") (name "Net-(U42-+VO)") (class "Default")
      (node (ref "R28") (pin "1") (pinfunction "1_1") (pintype "input"))
      (node (ref "U42") (pin "4") (pinfunction "+VO_4") (pintype "unspecified"))
    )
    (net (code "62") (name "Net-(U43-ADJ(GND))") (class "Default")
      (node (ref "R27") (pin "3") (pinfunction "3_3") (pintype "unspecified"))
      (node (ref "U41") (pin "1") (pinfunction "1_1") (pintype "unspecified"))
      (node (ref "U43") (pin "1") (pinfunction "ADJ(GND)_1") (pintype "unspecified"))
    )
    (net (code "63") (name "Net-(U43-VIN)") (class "Default")
      (node (ref "C101") (pin "2") (pinfunction "2_2") (pintype "unspecified"))
      (node (ref "R28") (pin "2") (pinfunction "2_2") (pintype "input"))
      (node (ref "U43") (pin "3") (pinfunction "VIN_3") (pintype "unspecified"))
    )
    (net (code "64") (name "Net-(U44-ADJ(GND))") (class "Default")
      (node (ref "R30") (pin "3") (pinfunction "3_3") (pintype "unspecified"))
      (node (ref "U44") (pin "1") (pinfunction "ADJ(GND)_1") (pintype "unspecified"))
      (node (ref "U46") (pin "1") (pinfunction "1_1") (pintype "unspecified"))
    )
    (net (code "65") (name "Net-(U44-VIN)") (class "Default")
      (node (ref "C104") (pin "2") (pinfunction "2_2") (pintype "unspecified"))
      (node (ref "R29") (pin "2") (pinfunction "2_2") (pintype "input"))
      (node (ref "U44") (pin "3") (pinfunction "VIN_3") (pintype "unspecified"))
    )
    (net (code "66") (name "Net-(U45-+VO)") (class "Default")
      (node (ref "R29") (pin "1") (pinfunction "1_1") (pintype "input"))
      (node (ref "U45") (pin "4") (pinfunction "+VO_4") (pintype "unspecified"))
    )
    (net (code "67") (name "unconnected-(U2-TAB-Pad4)") (class "Default")
      (node (ref "U2") (pin "4") (pinfunction "TAB_4") (pintype "unspecified+no_connect"))
    )
    (net (code "68") (name "unconnected-(U5-TAB-Pad4)") (class "Default")
      (node (ref "U5") (pin "4") (pinfunction "TAB_4") (pintype "unspecified+no_connect"))
    )
    (net (code "69") (name "unconnected-(U8-TAB-Pad4)") (class "Default")
      (node (ref "U8") (pin "4") (pinfunction "TAB_4") (pintype "unspecified+no_connect"))
    )
    (net (code "70") (name "unconnected-(U13-TAB-Pad4)") (class "Default")
      (node (ref "U13") (pin "4") (pinfunction "TAB_4") (pintype "unspecified+no_connect"))
    )
    (net (code "71") (name "unconnected-(U14-TAB-Pad4)") (class "Default")
      (node (ref "U14") (pin "4") (pinfunction "TAB_4") (pintype "unspecified+no_connect"))
    )
    (net (code "72") (name "unconnected-(U19-TAB-Pad4)") (class "Default")
      (node (ref "U19") (pin "4") (pinfunction "TAB_4") (pintype "unspecified+no_connect"))
    )
    (net (code "73") (name "unconnected-(U20-TAB-Pad4)") (class "Default")
      (node (ref "U20") (pin "4") (pinfunction "TAB_4") (pintype "unspecified+no_connect"))
    )
    (net (code "74") (name "unconnected-(U25-TAB-Pad4)") (class "Default")
      (node (ref "U25") (pin "4") (pinfunction "TAB_4") (pintype "unspecified+no_connect"))
    )
    (net (code "75") (name "unconnected-(U26-TAB-Pad4)") (class "Default")
      (node (ref "U26") (pin "4") (pinfunction "TAB_4") (pintype "unspecified+no_connect"))
    )
    (net (code "76") (name "unconnected-(U31-TAB-Pad4)") (class "Default")
      (node (ref "U31") (pin "4") (pinfunction "TAB_4") (pintype "unspecified+no_connect"))
    )
    (net (code "77") (name "unconnected-(U32-TAB-Pad4)") (class "Default")
      (node (ref "U32") (pin "4") (pinfunction "TAB_4") (pintype "unspecified+no_connect"))
    )
    (net (code "78") (name "unconnected-(U37-TAB-Pad4)") (class "Default")
      (node (ref "U37") (pin "4") (pinfunction "TAB_4") (pintype "unspecified+no_connect"))
    )
    (net (code "79") (name "unconnected-(U38-TAB-Pad4)") (class "Default")
      (node (ref "U38") (pin "4") (pinfunction "TAB_4") (pintype "unspecified+no_connect"))
    )
    (net (code "80") (name "unconnected-(U43-TAB-Pad4)") (class "Default")
      (node (ref "U43") (pin "4") (pinfunction "TAB_4") (pintype "unspecified+no_connect"))
    )
    (net (code "81") (name "unconnected-(U44-TAB-Pad4)") (class "Default")
      (node (ref "U44") (pin "4") (pinfunction "TAB_4") (pintype "unspecified+no_connect"))
    )
  )
)
